# GRBLShieldv2.net
KiCad netlist of a schematic drawn in EAGLE
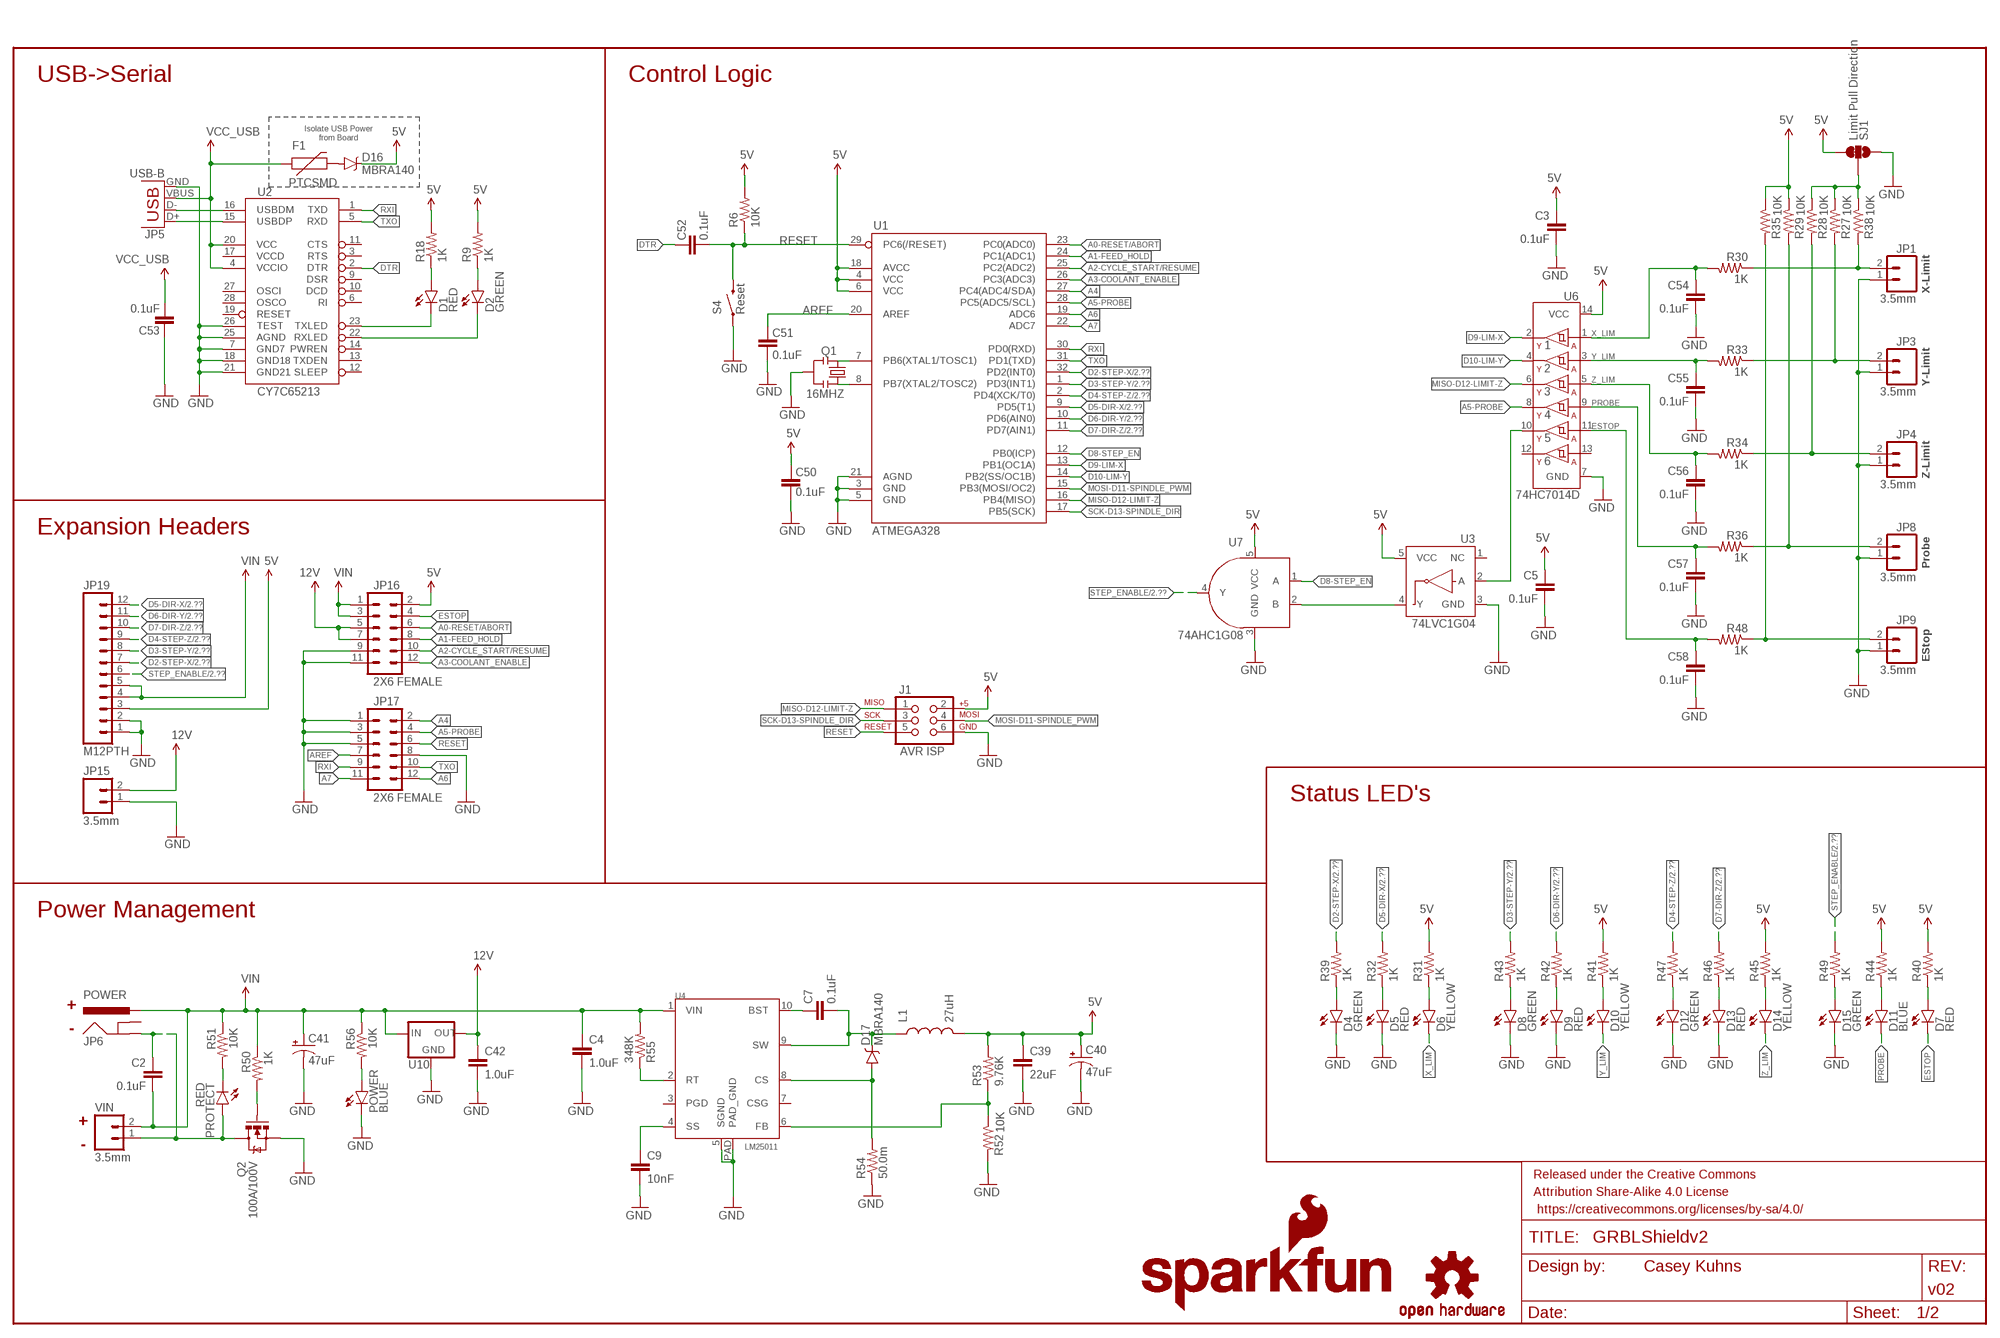
[diagram p0: schematic, sheet 1]
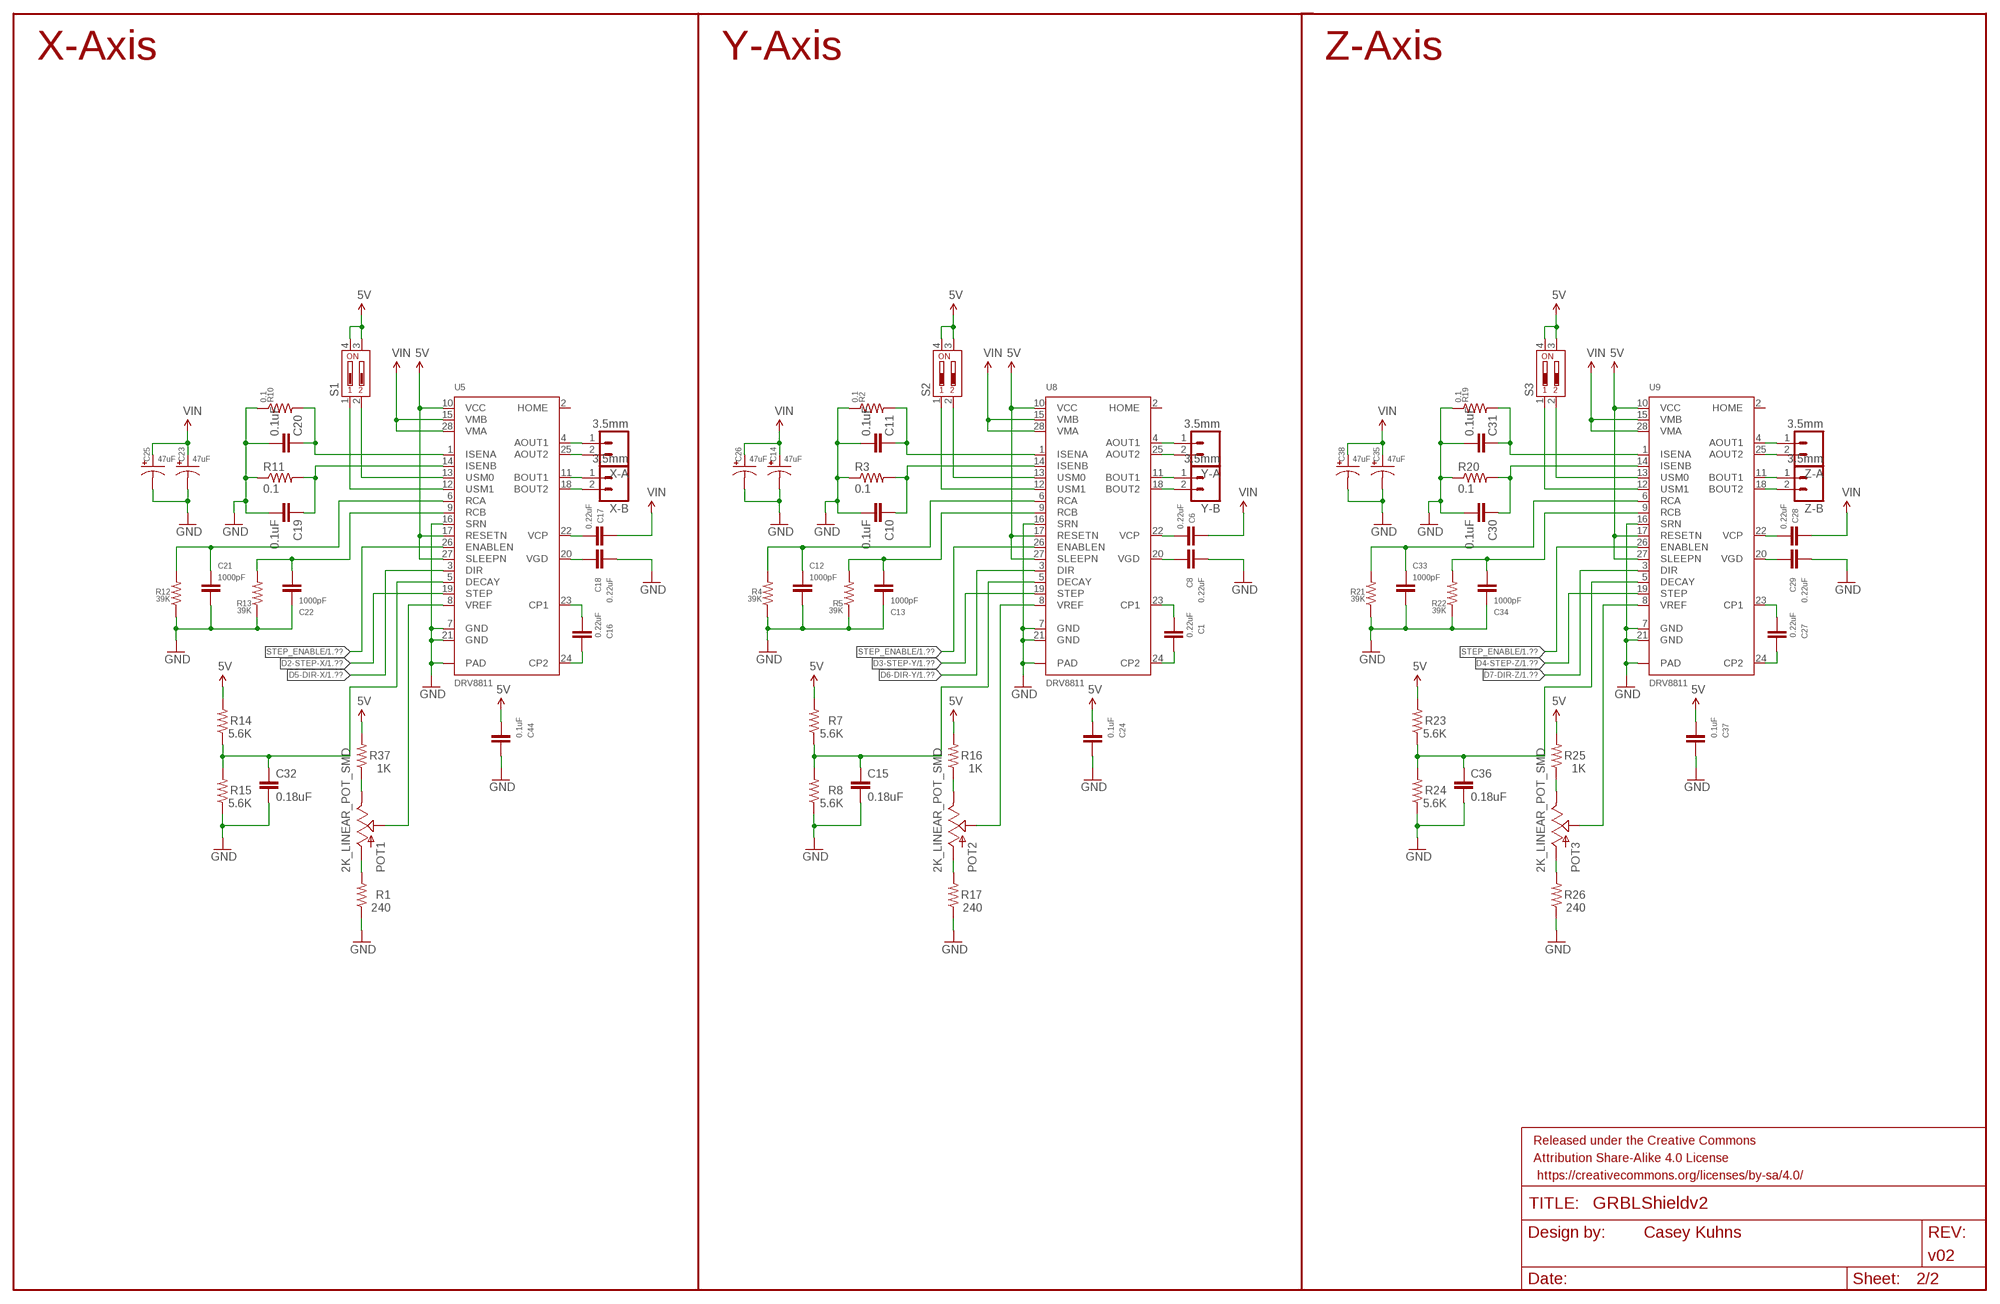
[diagram p1: schematic, sheet 2]

(export (version "E")
  (design (tool "Eeschema 10.0.6"))
  (components
    (comp (ref "C2")
      (value "0.1uF")
      (footprint "eagle-import:0603-CAP")
      (libsource (lib "eagle-import") (part "0.1UF-100V-10%(0603)"))
    )
    (comp (ref "C3")
      (value "0.1uF")
      (footprint "eagle-import:0603-CAP")
      (libsource (lib "eagle-import") (part "0.1UF-25V(+80/-20%)(0603)"))
    )
    (comp (ref "C4")
      (value "1.0uF")
      (footprint "eagle-import:1206")
      (libsource (lib "eagle-import") (part "1.0UF50V10%(1206)"))
    )
    (comp (ref "C5")
      (value "0.1uF")
      (footprint "eagle-import:0603-CAP")
      (libsource (lib "eagle-import") (part "0.1UF-25V(+80/-20%)(0603)"))
    )
    (comp (ref "C7")
      (value "0.1uF")
      (footprint "eagle-import:0603-CAP")
      (libsource (lib "eagle-import") (part "0.1UF-25V(+80/-20%)(0603)"))
    )
    (comp (ref "C9")
      (value "10nF")
      (footprint "eagle-import:0603-CAP")
      (libsource (lib "eagle-import") (part "10NF/10000PF-50V-10%(0603)"))
    )
    (comp (ref "C39")
      (value "22uF")
      (footprint "eagle-import:1210")
      (libsource (lib "eagle-import") (part "22UF-16V-20%-(1210)"))
    )
    (comp (ref "C40")
      (value "47uF")
      (footprint "eagle-import:PANASONIC_D")
      (libsource (lib "eagle-import") (part "47UF-50V-20%(ELECT)"))
    )
    (comp (ref "C41")
      (value "47uF")
      (footprint "eagle-import:PANASONIC_D")
      (libsource (lib "eagle-import") (part "47UF-50V-20%(ELECT)"))
    )
    (comp (ref "C42")
      (value "1.0uF")
      (footprint "eagle-import:1206")
      (libsource (lib "eagle-import") (part "1.0UF50V10%(1206)"))
    )
    (comp (ref "C50")
      (value "0.1uF")
      (footprint "eagle-import:0603-CAP")
      (libsource (lib "eagle-import") (part "0.1UF-25V(+80/-20%)(0603)"))
    )
    (comp (ref "C51")
      (value "0.1uF")
      (footprint "eagle-import:0603-CAP")
      (libsource (lib "eagle-import") (part "0.1UF-25V(+80/-20%)(0603)"))
    )
    (comp (ref "C52")
      (value "0.1uF")
      (footprint "eagle-import:0603-CAP")
      (libsource (lib "eagle-import") (part "0.1UF-25V(+80/-20%)(0603)"))
    )
    (comp (ref "C53")
      (value "0.1uF")
      (footprint "eagle-import:0603-CAP")
      (libsource (lib "eagle-import") (part "0.1UF-25V(+80/-20%)(0603)"))
    )
    (comp (ref "C54")
      (value "0.1uF")
      (footprint "eagle-import:0603-CAP")
      (libsource (lib "eagle-import") (part "0.1UF-25V(+80/-20%)(0603)"))
    )
    (comp (ref "C55")
      (value "0.1uF")
      (footprint "eagle-import:0603-CAP")
      (libsource (lib "eagle-import") (part "0.1UF-25V(+80/-20%)(0603)"))
    )
    (comp (ref "C56")
      (value "0.1uF")
      (footprint "eagle-import:0603-CAP")
      (libsource (lib "eagle-import") (part "0.1UF-25V(+80/-20%)(0603)"))
    )
    (comp (ref "C57")
      (value "0.1uF")
      (footprint "eagle-import:0603-CAP")
      (libsource (lib "eagle-import") (part "0.1UF-25V(+80/-20%)(0603)"))
    )
    (comp (ref "C58")
      (value "0.1uF")
      (footprint "eagle-import:0603-CAP")
      (libsource (lib "eagle-import") (part "0.1UF-25V(+80/-20%)(0603)"))
    )
    (comp (ref "D1")
      (value "RED")
      (footprint "eagle-import:LED-1206")
      (libsource (lib "eagle-import") (part "LED-REDLILYPAD"))
    )
    (comp (ref "D2")
      (value "GREEN")
      (footprint "eagle-import:LED-1206")
      (libsource (lib "eagle-import") (part "LED-GREENLILYPAD"))
    )
    (comp (ref "D4")
      (value "GREEN")
      (footprint "eagle-import:LED-1206")
      (libsource (lib "eagle-import") (part "LED-GREENLILYPAD"))
    )
    (comp (ref "D5")
      (value "RED")
      (footprint "eagle-import:LED-1206")
      (libsource (lib "eagle-import") (part "LED-REDLILYPAD"))
    )
    (comp (ref "D6")
      (value "YELLOW")
      (footprint "eagle-import:LED-1206")
      (libsource (lib "eagle-import") (part "LED-YELLOWLILYPAD"))
    )
    (comp (ref "D7")
      (value "RED")
      (footprint "eagle-import:LED-1206")
      (libsource (lib "eagle-import") (part "LED-REDLILYPAD"))
    )
    (comp (ref "D8")
      (value "GREEN")
      (footprint "eagle-import:LED-1206")
      (libsource (lib "eagle-import") (part "LED-GREENLILYPAD"))
    )
    (comp (ref "D9")
      (value "RED")
      (footprint "eagle-import:LED-1206")
      (libsource (lib "eagle-import") (part "LED-REDLILYPAD"))
    )
    (comp (ref "D10")
      (value "YELLOW")
      (footprint "eagle-import:LED-1206")
      (libsource (lib "eagle-import") (part "LED-YELLOWLILYPAD"))
    )
    (comp (ref "D11")
      (value "BLUE")
      (footprint "eagle-import:LED-1206")
      (libsource (lib "eagle-import") (part "LED-BLUE1206"))
    )
    (comp (ref "D12")
      (value "GREEN")
      (footprint "eagle-import:LED-1206")
      (libsource (lib "eagle-import") (part "LED-GREENLILYPAD"))
    )
    (comp (ref "D13")
      (value "RED")
      (footprint "eagle-import:LED-1206")
      (libsource (lib "eagle-import") (part "LED-REDLILYPAD"))
    )
    (comp (ref "D14")
      (value "YELLOW")
      (footprint "eagle-import:LED-1206")
      (libsource (lib "eagle-import") (part "LED-YELLOWLILYPAD"))
    )
    (comp (ref "D15")
      (value "GREEN")
      (footprint "eagle-import:LED-1206")
      (libsource (lib "eagle-import") (part "LED-GREENLILYPAD"))
    )
    (comp (ref "D16")
      (value "MBRA140")
      (footprint "eagle-import:SMA-DIODE")
      (libsource (lib "eagle-import") (part "DIODE-SCHOTTKY-MBRA140"))
    )
    (comp (ref "D17")
      (value "MBRA140")
      (footprint "eagle-import:SMA-DIODE")
      (libsource (lib "eagle-import") (part "DIODE-SCHOTTKY-MBRA140"))
    )
    (comp (ref "F1")
      (value "PTCSMD")
      (footprint "eagle-import:PTC-1206")
      (libsource (lib "eagle-import") (part "PTCSMD"))
    )
    (comp (ref "FRAME1")
      (value "FRAME-LEDGER")
      (footprint "eagle-import:CREATIVE_COMMONS")
      (fields (field (name "DESIGNER") "Casey Kuhns") (field (name "VERSION") "v02"))
      (libsource (lib "eagle-import") (part "FRAME-LEDGER"))
    )
    (comp (ref "J1")
      (value "AVR ISP")
      (footprint "eagle-import:2X3")
      (libsource (lib "eagle-import") (part "AVR_SPI_PRG_6PTH"))
    )
    (comp (ref "JP1")
      (value "3.5mm")
      (footprint "eagle-import:SCREWTERMINAL-3.5MM-2_LOCK")
      (libsource (lib "eagle-import") (part "M023.5MM_LOCK"))
    )
    (comp (ref "JP3")
      (value "3.5mm")
      (footprint "eagle-import:SCREWTERMINAL-3.5MM-2_LOCK")
      (libsource (lib "eagle-import") (part "M023.5MM_LOCK"))
    )
    (comp (ref "JP4")
      (value "3.5mm")
      (footprint "eagle-import:SCREWTERMINAL-3.5MM-2_LOCK")
      (libsource (lib "eagle-import") (part "M023.5MM_LOCK"))
    )
    (comp (ref "JP5")
      (value "USB-B")
      (footprint "eagle-import:USB-B-PTH")
      (libsource (lib "eagle-import") (part "USBPTH"))
    )
    (comp (ref "JP6")
      (value "POWER")
      (footprint "eagle-import:POWER_JACK_PTH_LOCK")
      (libsource (lib "eagle-import") (part "POWER_JACKPTH_LOCK"))
    )
    (comp (ref "JP8")
      (value "3.5mm")
      (footprint "eagle-import:SCREWTERMINAL-3.5MM-2_LOCK")
      (libsource (lib "eagle-import") (part "M023.5MM_LOCK"))
    )
    (comp (ref "JP9")
      (value "3.5mm")
      (footprint "eagle-import:SCREWTERMINAL-3.5MM-2_LOCK")
      (libsource (lib "eagle-import") (part "M023.5MM_LOCK"))
    )
    (comp (ref "JP15")
      (value "3.5mm")
      (footprint "eagle-import:SCREWTERMINAL-3.5MM-2_LOCK")
      (libsource (lib "eagle-import") (part "M023.5MM_LOCK"))
    )
    (comp (ref "JP16")
      (value "2X6 FEMALE")
      (footprint "eagle-import:2X6")
      (libsource (lib "eagle-import") (part "M06X2PTH_FEMALE"))
    )
    (comp (ref "JP17")
      (value "2X6 FEMALE")
      (footprint "eagle-import:2X6")
      (libsource (lib "eagle-import") (part "M06X2PTH_FEMALE"))
    )
    (comp (ref "JP19")
      (value "M12PTH")
      (footprint "eagle-import:1X12")
      (libsource (lib "eagle-import") (part "M12PTH"))
    )
    (comp (ref "L1")
      (value "27uH")
      (footprint "eagle-import:INDUCTOR_SDR1307")
      (libsource (lib "eagle-import") (part "INDUCTORSDR13-7-270ML"))
    )
    (comp (ref "LOGO1")
      (value "OSHW-LOGOM")
      (footprint "eagle-import:OSHW-LOGO-M")
      (libsource (lib "eagle-import") (part "OSHW-LOGOM"))
    )
    (comp (ref "LOGO2")
      (value "SFE_LOGO_NAME_FLAME.2_INCH")
      (footprint "eagle-import:SFE_LOGO_NAME_FLAME_.2")
      (libsource (lib "eagle-import") (part "SFE_LOGO_NAME_FLAME.2_INCH"))
    )
    (comp (ref "POWER")
      (value "BLUE")
      (footprint "eagle-import:LED-1206")
      (libsource (lib "eagle-import") (part "LED-BLUE1206"))
    )
    (comp (ref "PROTECT")
      (value "RED")
      (footprint "eagle-import:LED-1206")
      (libsource (lib "eagle-import") (part "LED-REDLILYPAD"))
    )
    (comp (ref "Q1")
      (value "16MHZ")
      (footprint "eagle-import:RESONATOR-SMD")
      (libsource (lib "eagle-import") (part "RESONATOR16MHZ"))
    )
    (comp (ref "Q2")
      (value "100A/100V")
      (footprint "eagle-import:TO-263_D2PAK")
      (libsource (lib "eagle-import") (part "MOSFET-NCHANNELPSMN7R0"))
    )
    (comp (ref "R6")
      (value "10K")
      (footprint "eagle-import:0603-RES")
      (libsource (lib "eagle-import") (part "10KOHM-1/10W-1%(0603)0603"))
    )
    (comp (ref "R9")
      (value "1K")
      (footprint "eagle-import:0603-RES")
      (libsource (lib "eagle-import") (part "1KOHM1/10W1%(0603)"))
    )
    (comp (ref "R18")
      (value "1K")
      (footprint "eagle-import:0603-RES")
      (libsource (lib "eagle-import") (part "1KOHM1/10W1%(0603)"))
    )
    (comp (ref "R27")
      (value "10K")
      (footprint "eagle-import:0603-RES")
      (libsource (lib "eagle-import") (part "10KOHM-1/10W-1%(0603)0603"))
    )
    (comp (ref "R28")
      (value "10K")
      (footprint "eagle-import:0603-RES")
      (libsource (lib "eagle-import") (part "10KOHM-1/10W-1%(0603)0603"))
    )
    (comp (ref "R29")
      (value "10K")
      (footprint "eagle-import:0603-RES")
      (libsource (lib "eagle-import") (part "10KOHM-1/10W-1%(0603)0603"))
    )
    (comp (ref "R30")
      (value "1K")
      (footprint "eagle-import:0603-RES")
      (libsource (lib "eagle-import") (part "1KOHM1/10W1%(0603)"))
    )
    (comp (ref "R31")
      (value "1K")
      (footprint "eagle-import:0603-RES")
      (libsource (lib "eagle-import") (part "1KOHM-1/10W-1%(0603)"))
    )
    (comp (ref "R32")
      (value "1K")
      (footprint "eagle-import:0603-RES")
      (libsource (lib "eagle-import") (part "1KOHM-1/10W-1%(0603)"))
    )
    (comp (ref "R33")
      (value "1K")
      (footprint "eagle-import:0603-RES")
      (libsource (lib "eagle-import") (part "1KOHM1/10W1%(0603)"))
    )
    (comp (ref "R34")
      (value "1K")
      (footprint "eagle-import:0603-RES")
      (libsource (lib "eagle-import") (part "1KOHM1/10W1%(0603)"))
    )
    (comp (ref "R35")
      (value "10K")
      (footprint "eagle-import:0603-RES")
      (libsource (lib "eagle-import") (part "10KOHM-1/10W-1%(0603)0603"))
    )
    (comp (ref "R36")
      (value "1K")
      (footprint "eagle-import:0603-RES")
      (libsource (lib "eagle-import") (part "1KOHM1/10W1%(0603)"))
    )
    (comp (ref "R38")
      (value "10K")
      (footprint "eagle-import:0603-RES")
      (libsource (lib "eagle-import") (part "10KOHM-1/10W-1%(0603)0603"))
    )
    (comp (ref "R39")
      (value "1K")
      (footprint "eagle-import:0603-RES")
      (libsource (lib "eagle-import") (part "1KOHM-1/10W-1%(0603)"))
    )
    (comp (ref "R40")
      (value "1K")
      (footprint "eagle-import:0603-RES")
      (libsource (lib "eagle-import") (part "1KOHM-1/10W-1%(0603)"))
    )
    (comp (ref "R41")
      (value "1K")
      (footprint "eagle-import:0603-RES")
      (libsource (lib "eagle-import") (part "1KOHM-1/10W-1%(0603)"))
    )
    (comp (ref "R42")
      (value "1K")
      (footprint "eagle-import:0603-RES")
      (libsource (lib "eagle-import") (part "1KOHM-1/10W-1%(0603)"))
    )
    (comp (ref "R43")
      (value "1K")
      (footprint "eagle-import:0603-RES")
      (libsource (lib "eagle-import") (part "1KOHM-1/10W-1%(0603)"))
    )
    (comp (ref "R44")
      (value "1K")
      (footprint "eagle-import:0603-RES")
      (libsource (lib "eagle-import") (part "1KOHM-1/10W-1%(0603)"))
    )
    (comp (ref "R45")
      (value "1K")
      (footprint "eagle-import:0603-RES")
      (libsource (lib "eagle-import") (part "1KOHM-1/10W-1%(0603)"))
    )
    (comp (ref "R46")
      (value "1K")
      (footprint "eagle-import:0603-RES")
      (libsource (lib "eagle-import") (part "1KOHM-1/10W-1%(0603)"))
    )
    (comp (ref "R47")
      (value "1K")
      (footprint "eagle-import:0603-RES")
      (libsource (lib "eagle-import") (part "1KOHM-1/10W-1%(0603)"))
    )
    (comp (ref "R48")
      (value "1K")
      (footprint "eagle-import:0603-RES")
      (libsource (lib "eagle-import") (part "1KOHM1/10W1%(0603)"))
    )
    (comp (ref "R49")
      (value "1K")
      (footprint "eagle-import:0603-RES")
      (libsource (lib "eagle-import") (part "1KOHM-1/10W-1%(0603)"))
    )
    (comp (ref "R50")
      (value "1K")
      (footprint "eagle-import:0603-RES")
      (libsource (lib "eagle-import") (part "1KOHM1/10W1%(0603)"))
    )
    (comp (ref "R51")
      (value "10K")
      (footprint "eagle-import:0603-RES")
      (libsource (lib "eagle-import") (part "10KOHM-1/10W-1%(0603)0603"))
    )
    (comp (ref "R52")
      (value "10K")
      (footprint "eagle-import:0603-RES")
      (libsource (lib "eagle-import") (part "10KOHM-1/10W-1%(0603)0603"))
    )
    (comp (ref "R53")
      (value "9.76K")
      (footprint "eagle-import:0603-RES")
      (libsource (lib "eagle-import") (part "RESISTOR0603-RES"))
    )
    (comp (ref "R54")
      (value "50.0m")
      (footprint "eagle-import:0603-RES")
      (libsource (lib "eagle-import") (part "RESISTOR0603-RES"))
    )
    (comp (ref "R55")
      (value "348K")
      (footprint "eagle-import:0603-RES")
      (libsource (lib "eagle-import") (part "RESISTOR0603-RES"))
    )
    (comp (ref "R56")
      (value "10K")
      (footprint "eagle-import:0603-RES")
      (libsource (lib "eagle-import") (part "10KOHM-1/10W-1%(0603)0603"))
    )
    (comp (ref "S4")
      (value "Reset")
      (footprint "eagle-import:TACTILE-SWITCH-SMD")
      (libsource (lib "eagle-import") (part "SWITCH-MOMENTARY-2SMD"))
    )
    (comp (ref "SJ1")
      (value "Limit Pull Direction")
      (footprint "eagle-import:PAD-JUMPER-3-2OF3_NC_BY_TRACE_YES_SILK_LARGE")
      (libsource (lib "eagle-import") (part "JUMPER-PAD-3-2OF3_NC_BY_TRACE_LARGE"))
    )
    (comp (ref "U1")
      (value "ATMEGA328")
      (footprint "eagle-import:TQFP32-08")
      (libsource (lib "eagle-import") (part "ATMEGA328_SMT"))
    )
    (comp (ref "U2")
      (value "CY7C65213")
      (footprint "eagle-import:SSOP28DB")
      (libsource (lib "eagle-import") (part "CY7C65213"))
    )
    (comp (ref "U3")
      (value "74LVC1G04")
      (footprint "eagle-import:SOT353")
      (libsource (lib "eagle-import") (part "INVERTER_SOT353-5"))
    )
    (comp (ref "U4")
      (value "LM25011")
      (footprint "eagle-import:HVSS0P-10")
      (libsource (lib "eagle-import") (part "LM25011"))
    )
    (comp (ref "U6")
      (value "74HC7014D")
      (footprint "eagle-import:SOIC-14")
      (libsource (lib "eagle-import") (part "74HC7014D"))
    )
    (comp (ref "U7")
      (value "74AHC1G08")
      (footprint "eagle-import:SOT23-5")
      (libsource (lib "eagle-import") (part "74AHC1G08"))
    )
    (comp (ref "U10")
      (value "V_REG_78XX7812")
      (footprint "eagle-import:TO-252")
      (libsource (lib "eagle-import") (part "V_REG_78XX7812"))
    )
    (comp (ref "VIN")
      (value "3.5mm")
      (footprint "eagle-import:SCREWTERMINAL-3.5MM-2_LOCK")
      (libsource (lib "eagle-import") (part "M023.5MM_LOCK"))
    )
    (comp (ref "C1")
      (value "0.22uF")
      (footprint "eagle-import:0603-CAP")
      (libsource (lib "eagle-import") (part "0.22UF50V-20%,+80%(0603)"))
    )
    (comp (ref "C6")
      (value "0.22uF")
      (footprint "eagle-import:0603-CAP")
      (libsource (lib "eagle-import") (part "0.22UF50V-20%,+80%(0603)"))
    )
    (comp (ref "C8")
      (value "0.22uF")
      (footprint "eagle-import:0603-CAP")
      (libsource (lib "eagle-import") (part "0.22UF50V-20%,+80%(0603)"))
    )
    (comp (ref "C10")
      (value "0.1uF")
      (footprint "eagle-import:0603-CAP")
      (libsource (lib "eagle-import") (part "0.1UF-25V(+80/-20%)(0603)"))
    )
    (comp (ref "C11")
      (value "0.1uF")
      (footprint "eagle-import:0603-CAP")
      (libsource (lib "eagle-import") (part "0.1UF-25V(+80/-20%)(0603)"))
    )
    (comp (ref "C12")
      (value "1000pF")
      (footprint "eagle-import:0603-CAP")
      (libsource (lib "eagle-import") (part "1NF/1000PF-50V-10%(0603)"))
    )
    (comp (ref "C13")
      (value "1000pF")
      (footprint "eagle-import:0603-CAP")
      (libsource (lib "eagle-import") (part "1NF/1000PF-50V-10%(0603)"))
    )
    (comp (ref "C14")
      (value "47uF")
      (footprint "eagle-import:PANASONIC_D")
      (libsource (lib "eagle-import") (part "47UF-50V-20%(ELECT)"))
    )
    (comp (ref "C15")
      (value "0.18uF")
      (footprint "eagle-import:0603-CAP")
      (libsource (lib "eagle-import") (part "CAP0603-CAP"))
    )
    (comp (ref "C16")
      (value "0.22uF")
      (footprint "eagle-import:0603-CAP")
      (libsource (lib "eagle-import") (part "0.22UF50V-20%,+80%(0603)"))
    )
    (comp (ref "C17")
      (value "0.22uF")
      (footprint "eagle-import:0603-CAP")
      (libsource (lib "eagle-import") (part "0.22UF50V-20%,+80%(0603)"))
    )
    (comp (ref "C18")
      (value "0.22uF")
      (footprint "eagle-import:0603-CAP")
      (libsource (lib "eagle-import") (part "0.22UF50V-20%,+80%(0603)"))
    )
    (comp (ref "C19")
      (value "0.1uF")
      (footprint "eagle-import:0603-CAP")
      (libsource (lib "eagle-import") (part "0.1UF-25V(+80/-20%)(0603)"))
    )
    (comp (ref "C20")
      (value "0.1uF")
      (footprint "eagle-import:0603-CAP")
      (libsource (lib "eagle-import") (part "0.1UF-25V(+80/-20%)(0603)"))
    )
    (comp (ref "C21")
      (value "1000pF")
      (footprint "eagle-import:0603-CAP")
      (libsource (lib "eagle-import") (part "1NF/1000PF-50V-10%(0603)"))
    )
    (comp (ref "C22")
      (value "1000pF")
      (footprint "eagle-import:0603-CAP")
      (libsource (lib "eagle-import") (part "1NF/1000PF-50V-10%(0603)"))
    )
    (comp (ref "C23")
      (value "47uF")
      (footprint "eagle-import:PANASONIC_D")
      (libsource (lib "eagle-import") (part "47UF-50V-20%(ELECT)"))
    )
    (comp (ref "C24")
      (value "0.1uF")
      (footprint "eagle-import:0603-CAP")
      (libsource (lib "eagle-import") (part "0.1UF-25V(+80/-20%)(0603)"))
    )
    (comp (ref "C25")
      (value "47uF")
      (footprint "eagle-import:PANASONIC_D")
      (libsource (lib "eagle-import") (part "47UF-50V-20%(ELECT)"))
    )
    (comp (ref "C26")
      (value "47uF")
      (footprint "eagle-import:PANASONIC_D")
      (libsource (lib "eagle-import") (part "47UF-50V-20%(ELECT)"))
    )
    (comp (ref "C27")
      (value "0.22uF")
      (footprint "eagle-import:0603-CAP")
      (libsource (lib "eagle-import") (part "0.22UF50V-20%,+80%(0603)"))
    )
    (comp (ref "C28")
      (value "0.22uF")
      (footprint "eagle-import:0603-CAP")
      (libsource (lib "eagle-import") (part "0.22UF50V-20%,+80%(0603)"))
    )
    (comp (ref "C29")
      (value "0.22uF")
      (footprint "eagle-import:0603-CAP")
      (libsource (lib "eagle-import") (part "0.22UF50V-20%,+80%(0603)"))
    )
    (comp (ref "C30")
      (value "0.1uF")
      (footprint "eagle-import:0603-CAP")
      (libsource (lib "eagle-import") (part "0.1UF-25V(+80/-20%)(0603)"))
    )
    (comp (ref "C31")
      (value "0.1uF")
      (footprint "eagle-import:0603-CAP")
      (libsource (lib "eagle-import") (part "0.1UF-25V(+80/-20%)(0603)"))
    )
    (comp (ref "C32")
      (value "0.18uF")
      (footprint "eagle-import:0603-CAP")
      (libsource (lib "eagle-import") (part "CAP0603-CAP"))
    )
    (comp (ref "C33")
      (value "1000pF")
      (footprint "eagle-import:0603-CAP")
      (libsource (lib "eagle-import") (part "1NF/1000PF-50V-10%(0603)"))
    )
    (comp (ref "C34")
      (value "1000pF")
      (footprint "eagle-import:0603-CAP")
      (libsource (lib "eagle-import") (part "1NF/1000PF-50V-10%(0603)"))
    )
    (comp (ref "C35")
      (value "47uF")
      (footprint "eagle-import:PANASONIC_D")
      (libsource (lib "eagle-import") (part "47UF-50V-20%(ELECT)"))
    )
    (comp (ref "C36")
      (value "0.18uF")
      (footprint "eagle-import:0603-CAP")
      (libsource (lib "eagle-import") (part "CAP0603-CAP"))
    )
    (comp (ref "C37")
      (value "0.1uF")
      (footprint "eagle-import:0603-CAP")
      (libsource (lib "eagle-import") (part "0.1UF-25V(+80/-20%)(0603)"))
    )
    (comp (ref "C38")
      (value "47uF")
      (footprint "eagle-import:PANASONIC_D")
      (libsource (lib "eagle-import") (part "47UF-50V-20%(ELECT)"))
    )
    (comp (ref "C44")
      (value "0.1uF")
      (footprint "eagle-import:0603-CAP")
      (libsource (lib "eagle-import") (part "0.1UF-25V(+80/-20%)(0603)"))
    )
    (comp (ref "FRAME2")
      (value "FRAME-LEDGER")
      (footprint "eagle-import:CREATIVE_COMMONS")
      (fields (field (name "DESIGNER") "Casey Kuhns") (field (name "VERSION") "v02"))
      (libsource (lib "eagle-import") (part "FRAME-LEDGER"))
    )
    (comp (ref "POT1")
      (value "2K_LINEAR_POT_SMD")
      (footprint "eagle-import:TC33X")
      (libsource (lib "eagle-import") (part "2K_LINEAR_POT_SMD"))
    )
    (comp (ref "POT2")
      (value "2K_LINEAR_POT_SMD")
      (footprint "eagle-import:TC33X")
      (libsource (lib "eagle-import") (part "2K_LINEAR_POT_SMD"))
    )
    (comp (ref "POT3")
      (value "2K_LINEAR_POT_SMD")
      (footprint "eagle-import:TC33X")
      (libsource (lib "eagle-import") (part "2K_LINEAR_POT_SMD"))
    )
    (comp (ref "R1")
      (value "240")
      (footprint "eagle-import:0603-RES")
      (libsource (lib "eagle-import") (part "240OHM1/10W1%(0603)"))
    )
    (comp (ref "R2")
      (value "0.1")
      (footprint "eagle-import:1210")
      (libsource (lib "eagle-import") (part "0.1OHM-1/2W-1%(1210)"))
    )
    (comp (ref "R3")
      (value "0.1")
      (footprint "eagle-import:1210")
      (libsource (lib "eagle-import") (part "0.1OHM-1/2W-1%(1210)"))
    )
    (comp (ref "R4")
      (value "39K")
      (footprint "eagle-import:0603")
      (libsource (lib "eagle-import") (part "39KOHM-1/10W-1%(0603)"))
    )
    (comp (ref "R5")
      (value "39K")
      (footprint "eagle-import:0603")
      (libsource (lib "eagle-import") (part "39KOHM-1/10W-1%(0603)"))
    )
    (comp (ref "R7")
      (value "5.6K")
      (footprint "eagle-import:0603")
      (libsource (lib "eagle-import") (part "5.6KOHM-1/10W-1%(0603)"))
    )
    (comp (ref "R8")
      (value "5.6K")
      (footprint "eagle-import:0603")
      (libsource (lib "eagle-import") (part "5.6KOHM-1/10W-1%(0603)"))
    )
    (comp (ref "R10")
      (value "0.1")
      (footprint "eagle-import:1210")
      (libsource (lib "eagle-import") (part "0.1OHM-1/2W-1%(1210)"))
    )
    (comp (ref "R11")
      (value "0.1")
      (footprint "eagle-import:1210")
      (libsource (lib "eagle-import") (part "0.1OHM-1/2W-1%(1210)"))
    )
    (comp (ref "R12")
      (value "39K")
      (footprint "eagle-import:0603")
      (libsource (lib "eagle-import") (part "39KOHM-1/10W-1%(0603)"))
    )
    (comp (ref "R13")
      (value "39K")
      (footprint "eagle-import:0603")
      (libsource (lib "eagle-import") (part "39KOHM-1/10W-1%(0603)"))
    )
    (comp (ref "R14")
      (value "5.6K")
      (footprint "eagle-import:0603")
      (libsource (lib "eagle-import") (part "5.6KOHM-1/10W-1%(0603)"))
    )
    (comp (ref "R15")
      (value "5.6K")
      (footprint "eagle-import:0603")
      (libsource (lib "eagle-import") (part "5.6KOHM-1/10W-1%(0603)"))
    )
    (comp (ref "R16")
      (value "1K")
      (footprint "eagle-import:0603-RES")
      (libsource (lib "eagle-import") (part "1KOHM-1/10W-1%(0603)"))
    )
    (comp (ref "R17")
      (value "240")
      (footprint "eagle-import:0603-RES")
      (libsource (lib "eagle-import") (part "240OHM1/10W1%(0603)"))
    )
    (comp (ref "R19")
      (value "0.1")
      (footprint "eagle-import:1210")
      (libsource (lib "eagle-import") (part "0.1OHM-1/2W-1%(1210)"))
    )
    (comp (ref "R20")
      (value "0.1")
      (footprint "eagle-import:1210")
      (libsource (lib "eagle-import") (part "0.1OHM-1/2W-1%(1210)"))
    )
    (comp (ref "R21")
      (value "39K")
      (footprint "eagle-import:0603")
      (libsource (lib "eagle-import") (part "39KOHM-1/10W-1%(0603)"))
    )
    (comp (ref "R22")
      (value "39K")
      (footprint "eagle-import:0603")
      (libsource (lib "eagle-import") (part "39KOHM-1/10W-1%(0603)"))
    )
    (comp (ref "R23")
      (value "5.6K")
      (footprint "eagle-import:0603")
      (libsource (lib "eagle-import") (part "5.6KOHM-1/10W-1%(0603)"))
    )
    (comp (ref "R24")
      (value "5.6K")
      (footprint "eagle-import:0603")
      (libsource (lib "eagle-import") (part "5.6KOHM-1/10W-1%(0603)"))
    )
    (comp (ref "R25")
      (value "1K")
      (footprint "eagle-import:0603-RES")
      (libsource (lib "eagle-import") (part "1KOHM-1/10W-1%(0603)"))
    )
    (comp (ref "R26")
      (value "240")
      (footprint "eagle-import:0603-RES")
      (libsource (lib "eagle-import") (part "240OHM1/10W1%(0603)"))
    )
    (comp (ref "R37")
      (value "1K")
      (footprint "eagle-import:0603-RES")
      (libsource (lib "eagle-import") (part "1KOHM-1/10W-1%(0603)"))
    )
    (comp (ref "S1")
      (value "2-POS-DIP")
      (footprint "eagle-import:CHS-02A")
      (libsource (lib "eagle-import") (part "2-POS-DIP"))
    )
    (comp (ref "S2")
      (value "2-POS-DIP")
      (footprint "eagle-import:CHS-02A")
      (libsource (lib "eagle-import") (part "2-POS-DIP"))
    )
    (comp (ref "S3")
      (value "2-POS-DIP")
      (footprint "eagle-import:CHS-02A")
      (libsource (lib "eagle-import") (part "2-POS-DIP"))
    )
    (comp (ref "U5")
      (value "DRV8811")
      (footprint "eagle-import:HTSSOP28")
      (libsource (lib "eagle-import") (part "DRV8811"))
    )
    (comp (ref "U8")
      (value "DRV8811")
      (footprint "eagle-import:HTSSOP28")
      (libsource (lib "eagle-import") (part "DRV8811"))
    )
    (comp (ref "U9")
      (value "DRV8811")
      (footprint "eagle-import:HTSSOP28")
      (libsource (lib "eagle-import") (part "DRV8811"))
    )
    (comp (ref "X-A")
      (value "3.5mm")
      (footprint "eagle-import:SCREWTERMINAL-3.5MM-2_LOCK")
      (libsource (lib "eagle-import") (part "M023.5MM_LOCK"))
    )
    (comp (ref "X-B")
      (value "3.5mm")
      (footprint "eagle-import:SCREWTERMINAL-3.5MM-2_LOCK")
      (libsource (lib "eagle-import") (part "M023.5MM_LOCK"))
    )
    (comp (ref "Y-A")
      (value "3.5mm")
      (footprint "eagle-import:SCREWTERMINAL-3.5MM-2_LOCK")
      (libsource (lib "eagle-import") (part "M023.5MM_LOCK"))
    )
    (comp (ref "Y-B")
      (value "3.5mm")
      (footprint "eagle-import:SCREWTERMINAL-3.5MM-2_LOCK")
      (libsource (lib "eagle-import") (part "M023.5MM_LOCK"))
    )
    (comp (ref "Z-A")
      (value "3.5mm")
      (footprint "eagle-import:SCREWTERMINAL-3.5MM-2_LOCK")
      (libsource (lib "eagle-import") (part "M023.5MM_LOCK"))
    )
    (comp (ref "Z-B")
      (value "3.5mm")
      (footprint "eagle-import:SCREWTERMINAL-3.5MM-2_LOCK")
      (libsource (lib "eagle-import") (part "M023.5MM_LOCK"))
    )
  )
  (nets
    (net (code "1") (name "5V") (class "Default")
      (node (ref "C24") (pin "1") (pinfunction "1_1") (pintype "passive"))
      (node (ref "C3") (pin "1") (pinfunction "1_1") (pintype "passive"))
      (node (ref "C37") (pin "1") (pinfunction "1_1") (pintype "passive"))
      (node (ref "C39") (pin "1") (pinfunction "1_1") (pintype "passive"))
      (node (ref "C40") (pin "+") (pinfunction "+_+") (pintype "passive"))
      (node (ref "C44") (pin "1") (pinfunction "1_1") (pintype "passive"))
      (node (ref "C5") (pin "1") (pinfunction "1_1") (pintype "passive"))
      (node (ref "C50") (pin "2") (pinfunction "2_2") (pintype "passive"))
      (node (ref "D16") (pin "C") (pinfunction "C_C") (pintype "passive"))
      (node (ref "J1") (pin "2") (pinfunction "2_2") (pintype "passive"))
      (node (ref "JP16") (pin "2") (pinfunction "2_2") (pintype "passive"))
      (node (ref "JP19") (pin "3") (pinfunction "3_3") (pintype "passive"))
      (node (ref "L1") (pin "P$2") (pinfunction "2_P$2") (pintype "passive"))
      (node (ref "R14") (pin "2") (pinfunction "2_2") (pintype "passive"))
      (node (ref "R16") (pin "2") (pinfunction "2_2") (pintype "passive"))
      (node (ref "R18") (pin "2") (pinfunction "2_2") (pintype "passive"))
      (node (ref "R23") (pin "2") (pinfunction "2_2") (pintype "passive"))
      (node (ref "R25") (pin "2") (pinfunction "2_2") (pintype "passive"))
      (node (ref "R29") (pin "1") (pinfunction "1_1") (pintype "passive"))
      (node (ref "R31") (pin "2") (pinfunction "2_2") (pintype "passive"))
      (node (ref "R35") (pin "1") (pinfunction "1_1") (pintype "passive"))
      (node (ref "R37") (pin "2") (pinfunction "2_2") (pintype "passive"))
      (node (ref "R40") (pin "2") (pinfunction "2_2") (pintype "passive"))
      (node (ref "R41") (pin "2") (pinfunction "2_2") (pintype "passive"))
      (node (ref "R44") (pin "2") (pinfunction "2_2") (pintype "passive"))
      (node (ref "R45") (pin "2") (pinfunction "2_2") (pintype "passive"))
      (node (ref "R53") (pin "2") (pinfunction "2_2") (pintype "passive"))
      (node (ref "R6") (pin "2") (pinfunction "2_2") (pintype "passive"))
      (node (ref "R7") (pin "2") (pinfunction "2_2") (pintype "passive"))
      (node (ref "R9") (pin "2") (pinfunction "2_2") (pintype "passive"))
      (node (ref "S1") (pin "3") (pinfunction "P$3_3") (pintype "bidirectional"))
      (node (ref "S1") (pin "4") (pinfunction "P$4_4") (pintype "bidirectional"))
      (node (ref "S2") (pin "3") (pinfunction "P$3_3") (pintype "bidirectional"))
      (node (ref "S2") (pin "4") (pinfunction "P$4_4") (pintype "bidirectional"))
      (node (ref "S3") (pin "3") (pinfunction "P$3_3") (pintype "bidirectional"))
      (node (ref "S3") (pin "4") (pinfunction "P$4_4") (pintype "bidirectional"))
      (node (ref "SJ1") (pin "3") (pinfunction "3_3") (pintype "passive"))
      (node (ref "U1") (pin "18") (pinfunction "AVCC_18") (pintype "bidirectional"))
      (node (ref "U1") (pin "4") (pinfunction "VCC_4") (pintype "bidirectional"))
      (node (ref "U1") (pin "6") (pinfunction "VCC_6") (pintype "bidirectional"))
      (node (ref "U3") (pin "5") (pinfunction "VCC_5") (pintype "bidirectional"))
      (node (ref "U5") (pin "10") (pinfunction "VCC_10") (pintype "bidirectional"))
      (node (ref "U5") (pin "17") (pinfunction "RESETN_17") (pintype "bidirectional"))
      (node (ref "U5") (pin "27") (pinfunction "SLEEPN_27") (pintype "bidirectional"))
      (node (ref "U6") (pin "14") (pinfunction "VCC_14") (pintype "power_in"))
      (node (ref "U7") (pin "5") (pinfunction "VCC_5") (pintype "bidirectional"))
      (node (ref "U8") (pin "10") (pinfunction "VCC_10") (pintype "bidirectional"))
      (node (ref "U8") (pin "17") (pinfunction "RESETN_17") (pintype "bidirectional"))
      (node (ref "U8") (pin "27") (pinfunction "SLEEPN_27") (pintype "bidirectional"))
      (node (ref "U9") (pin "10") (pinfunction "VCC_10") (pintype "bidirectional"))
      (node (ref "U9") (pin "17") (pinfunction "RESETN_17") (pintype "bidirectional"))
      (node (ref "U9") (pin "27") (pinfunction "SLEEPN_27") (pintype "bidirectional"))
    )
    (net (code "2") (name "A0-RESET{slash}ABORT") (class "Default")
      (node (ref "JP16") (pin "6") (pinfunction "6_6") (pintype "passive"))
      (node (ref "U1") (pin "23") (pinfunction "PC0(ADC0)_23") (pintype "bidirectional"))
    )
    (net (code "3") (name "A1-FEED_HOLD") (class "Default")
      (node (ref "JP16") (pin "8") (pinfunction "8_8") (pintype "passive"))
      (node (ref "U1") (pin "24") (pinfunction "PC1(ADC1)_24") (pintype "bidirectional"))
    )
    (net (code "4") (name "A2-CYCLE_START{slash}RESUME") (class "Default")
      (node (ref "JP16") (pin "10") (pinfunction "10_10") (pintype "passive"))
      (node (ref "U1") (pin "25") (pinfunction "PC2(ADC2)_25") (pintype "bidirectional"))
    )
    (net (code "5") (name "A3-COOLANT_ENABLE") (class "Default")
      (node (ref "JP16") (pin "12") (pinfunction "12_12") (pintype "passive"))
      (node (ref "U1") (pin "26") (pinfunction "PC3(ADC3)_26") (pintype "bidirectional"))
    )
    (net (code "6") (name "A4") (class "Default")
      (node (ref "JP17") (pin "2") (pinfunction "2_2") (pintype "passive"))
      (node (ref "U1") (pin "27") (pinfunction "PC4(ADC4/SDA)_27") (pintype "bidirectional"))
    )
    (net (code "7") (name "A5-PROBE") (class "Default")
      (node (ref "JP17") (pin "4") (pinfunction "4_4") (pintype "passive"))
      (node (ref "U1") (pin "28") (pinfunction "PC5(ADC5/SCL)_28") (pintype "bidirectional"))
      (node (ref "U6") (pin "8") (pinfunction "4Y_8") (pintype "output"))
    )
    (net (code "8") (name "A6") (class "Default")
      (node (ref "JP17") (pin "12") (pinfunction "12_12") (pintype "passive"))
      (node (ref "U1") (pin "19") (pinfunction "ADC6_19") (pintype "bidirectional"))
    )
    (net (code "9") (name "A7") (class "Default")
      (node (ref "JP17") (pin "11") (pinfunction "11_11") (pintype "passive"))
      (node (ref "U1") (pin "22") (pinfunction "ADC7_22") (pintype "bidirectional"))
    )
    (net (code "10") (name "AREF") (class "Default")
      (node (ref "C51") (pin "2") (pinfunction "2_2") (pintype "passive"))
      (node (ref "JP17") (pin "7") (pinfunction "7_7") (pintype "passive"))
      (node (ref "U1") (pin "20") (pinfunction "AREF_20") (pintype "bidirectional"))
    )
    (net (code "11") (name "D2-STEP-X") (class "Default")
      (node (ref "JP19") (pin "7") (pinfunction "7_7") (pintype "passive"))
      (node (ref "R39") (pin "2") (pinfunction "2_2") (pintype "passive"))
      (node (ref "U1") (pin "32") (pinfunction "PD2(INT0)_32") (pintype "bidirectional"))
      (node (ref "U5") (pin "19") (pinfunction "STEP_19") (pintype "bidirectional"))
    )
    (net (code "12") (name "D3-STEP-Y") (class "Default")
      (node (ref "JP19") (pin "8") (pinfunction "8_8") (pintype "passive"))
      (node (ref "R43") (pin "2") (pinfunction "2_2") (pintype "passive"))
      (node (ref "U1") (pin "1") (pinfunction "PD3(INT1)_1") (pintype "bidirectional"))
      (node (ref "U8") (pin "19") (pinfunction "STEP_19") (pintype "bidirectional"))
    )
    (net (code "13") (name "D4-STEP-Z") (class "Default")
      (node (ref "JP19") (pin "9") (pinfunction "9_9") (pintype "passive"))
      (node (ref "R47") (pin "2") (pinfunction "2_2") (pintype "passive"))
      (node (ref "U1") (pin "2") (pinfunction "PD4(XCK/T0)_2") (pintype "bidirectional"))
      (node (ref "U9") (pin "19") (pinfunction "STEP_19") (pintype "bidirectional"))
    )
    (net (code "14") (name "D5-DIR-X") (class "Default")
      (node (ref "JP19") (pin "12") (pinfunction "12_12") (pintype "passive"))
      (node (ref "R32") (pin "2") (pinfunction "2_2") (pintype "passive"))
      (node (ref "U1") (pin "9") (pinfunction "PD5(T1)_9") (pintype "bidirectional"))
      (node (ref "U5") (pin "3") (pinfunction "DIR_3") (pintype "bidirectional"))
    )
    (net (code "15") (name "D6-DIR-Y") (class "Default")
      (node (ref "JP19") (pin "11") (pinfunction "11_11") (pintype "passive"))
      (node (ref "R42") (pin "2") (pinfunction "2_2") (pintype "passive"))
      (node (ref "U1") (pin "10") (pinfunction "PD6(AIN0)_10") (pintype "bidirectional"))
      (node (ref "U8") (pin "3") (pinfunction "DIR_3") (pintype "bidirectional"))
    )
    (net (code "16") (name "D7-DIR-Z") (class "Default")
      (node (ref "JP19") (pin "10") (pinfunction "10_10") (pintype "passive"))
      (node (ref "R46") (pin "2") (pinfunction "2_2") (pintype "passive"))
      (node (ref "U1") (pin "11") (pinfunction "PD7(AIN1)_11") (pintype "bidirectional"))
      (node (ref "U9") (pin "3") (pinfunction "DIR_3") (pintype "bidirectional"))
    )
    (net (code "17") (name "D8-STEP_EN") (class "Default")
      (node (ref "U1") (pin "12") (pinfunction "PB0(ICP)_12") (pintype "bidirectional"))
      (node (ref "U7") (pin "1") (pinfunction "A_1") (pintype "bidirectional"))
    )
    (net (code "18") (name "D9-LIM-X") (class "Default")
      (node (ref "U1") (pin "13") (pinfunction "PB1(OC1A)_13") (pintype "bidirectional"))
      (node (ref "U6") (pin "2") (pinfunction "1Y_2") (pintype "output"))
    )
    (net (code "19") (name "D10-LIM-Y") (class "Default")
      (node (ref "U1") (pin "14") (pinfunction "PB2(SS/OC1B)_14") (pintype "bidirectional"))
      (node (ref "U6") (pin "4") (pinfunction "2Y_4") (pintype "output"))
    )
    (net (code "20") (name "DTR") (class "Default")
      (node (ref "C52") (pin "2") (pinfunction "2_2") (pintype "passive"))
      (node (ref "U2") (pin "2") (pinfunction "DTR_2") (pintype "output"))
    )
    (net (code "21") (name "ESTOP") (class "Default")
      (node (ref "C58") (pin "1") (pinfunction "1_1") (pintype "passive"))
      (node (ref "D7") (pin "C") (pinfunction "C_C") (pintype "passive"))
      (node (ref "JP16") (pin "4") (pinfunction "4_4") (pintype "passive"))
      (node (ref "R48") (pin "2") (pinfunction "2_2") (pintype "passive"))
      (node (ref "U6") (pin "11") (pinfunction "5A_11") (pintype "input"))
    )
    (net (code "22") (name "GND") (class "Default")
      (node (ref "C10") (pin "2") (pinfunction "2_2") (pintype "passive"))
      (node (ref "C11") (pin "2") (pinfunction "2_2") (pintype "passive"))
      (node (ref "C12") (pin "2") (pinfunction "2_2") (pintype "passive"))
      (node (ref "C13") (pin "2") (pinfunction "2_2") (pintype "passive"))
      (node (ref "C14") (pin "-") (pinfunction "-_-") (pintype "passive"))
      (node (ref "C15") (pin "2") (pinfunction "2_2") (pintype "passive"))
      (node (ref "C18") (pin "1") (pinfunction "1_1") (pintype "passive"))
      (node (ref "C19") (pin "2") (pinfunction "2_2") (pintype "passive"))
      (node (ref "C20") (pin "2") (pinfunction "2_2") (pintype "passive"))
      (node (ref "C21") (pin "2") (pinfunction "2_2") (pintype "passive"))
      (node (ref "C22") (pin "2") (pinfunction "2_2") (pintype "passive"))
      (node (ref "C23") (pin "-") (pinfunction "-_-") (pintype "passive"))
      (node (ref "C24") (pin "2") (pinfunction "2_2") (pintype "passive"))
      (node (ref "C25") (pin "-") (pinfunction "-_-") (pintype "passive"))
      (node (ref "C26") (pin "-") (pinfunction "-_-") (pintype "passive"))
      (node (ref "C29") (pin "1") (pinfunction "1_1") (pintype "passive"))
      (node (ref "C3") (pin "2") (pinfunction "2_2") (pintype "passive"))
      (node (ref "C30") (pin "2") (pinfunction "2_2") (pintype "passive"))
      (node (ref "C31") (pin "2") (pinfunction "2_2") (pintype "passive"))
      (node (ref "C32") (pin "2") (pinfunction "2_2") (pintype "passive"))
      (node (ref "C33") (pin "2") (pinfunction "2_2") (pintype "passive"))
      (node (ref "C34") (pin "2") (pinfunction "2_2") (pintype "passive"))
      (node (ref "C35") (pin "-") (pinfunction "-_-") (pintype "passive"))
      (node (ref "C36") (pin "2") (pinfunction "2_2") (pintype "passive"))
      (node (ref "C37") (pin "2") (pinfunction "2_2") (pintype "passive"))
      (node (ref "C38") (pin "-") (pinfunction "-_-") (pintype "passive"))
      (node (ref "C39") (pin "2") (pinfunction "2_2") (pintype "passive"))
      (node (ref "C4") (pin "2") (pinfunction "2_2") (pintype "passive"))
      (node (ref "C40") (pin "-") (pinfunction "-_-") (pintype "passive"))
      (node (ref "C41") (pin "-") (pinfunction "-_-") (pintype "passive"))
      (node (ref "C42") (pin "2") (pinfunction "2_2") (pintype "passive"))
      (node (ref "C44") (pin "2") (pinfunction "2_2") (pintype "passive"))
      (node (ref "C5") (pin "2") (pinfunction "2_2") (pintype "passive"))
      (node (ref "C50") (pin "1") (pinfunction "1_1") (pintype "passive"))
      (node (ref "C51") (pin "1") (pinfunction "1_1") (pintype "passive"))
      (node (ref "C53") (pin "2") (pinfunction "2_2") (pintype "passive"))
      (node (ref "C54") (pin "2") (pinfunction "2_2") (pintype "passive"))
      (node (ref "C55") (pin "2") (pinfunction "2_2") (pintype "passive"))
      (node (ref "C56") (pin "2") (pinfunction "2_2") (pintype "passive"))
      (node (ref "C57") (pin "2") (pinfunction "2_2") (pintype "passive"))
      (node (ref "C58") (pin "2") (pinfunction "2_2") (pintype "passive"))
      (node (ref "C8") (pin "1") (pinfunction "1_1") (pintype "passive"))
      (node (ref "C9") (pin "2") (pinfunction "2_2") (pintype "passive"))
      (node (ref "D12") (pin "C") (pinfunction "C_C") (pintype "passive"))
      (node (ref "D13") (pin "C") (pinfunction "C_C") (pintype "passive"))
      (node (ref "D15") (pin "C") (pinfunction "C_C") (pintype "passive"))
      (node (ref "D4") (pin "C") (pinfunction "C_C") (pintype "passive"))
      (node (ref "D5") (pin "C") (pinfunction "C_C") (pintype "passive"))
      (node (ref "D8") (pin "C") (pinfunction "C_C") (pintype "passive"))
      (node (ref "D9") (pin "C") (pinfunction "C_C") (pintype "passive"))
      (node (ref "J1") (pin "6") (pinfunction "6_6") (pintype "passive"))
      (node (ref "JP1") (pin "1") (pinfunction "1_1") (pintype "passive"))
      (node (ref "JP15") (pin "1") (pinfunction "1_1") (pintype "passive"))
      (node (ref "JP16") (pin "11") (pinfunction "11_11") (pintype "passive"))
      (node (ref "JP16") (pin "9") (pinfunction "9_9") (pintype "passive"))
      (node (ref "JP17") (pin "1") (pinfunction "1_1") (pintype "passive"))
      (node (ref "JP17") (pin "3") (pinfunction "3_3") (pintype "passive"))
      (node (ref "JP17") (pin "5") (pinfunction "5_5") (pintype "passive"))
      (node (ref "JP17") (pin "8") (pinfunction "8_8") (pintype "passive"))
      (node (ref "JP19") (pin "1") (pinfunction "1_1") (pintype "passive"))
      (node (ref "JP19") (pin "2") (pinfunction "2_2") (pintype "passive"))
      (node (ref "JP3") (pin "1") (pinfunction "1_1") (pintype "passive"))
      (node (ref "JP4") (pin "1") (pinfunction "1_1") (pintype "passive"))
      (node (ref "JP5") (pin "GND") (pinfunction "GND_GND") (pintype "bidirectional"))
      (node (ref "JP8") (pin "1") (pinfunction "1_1") (pintype "passive"))
      (node (ref "JP9") (pin "1") (pinfunction "1_1") (pintype "passive"))
      (node (ref "POWER") (pin "C") (pinfunction "C_C") (pintype "passive"))
      (node (ref "Q1") (pin "2") (pinfunction "2_2") (pintype "passive"))
      (node (ref "Q2") (pin "3") (pinfunction "S_3") (pintype "passive"))
      (node (ref "R1") (pin "1") (pinfunction "1_1") (pintype "passive"))
      (node (ref "R10") (pin "1") (pinfunction "1_1") (pintype "passive"))
      (node (ref "R11") (pin "1") (pinfunction "1_1") (pintype "passive"))
      (node (ref "R12") (pin "1") (pinfunction "1_1") (pintype "passive"))
      (node (ref "R13") (pin "1") (pinfunction "1_1") (pintype "passive"))
      (node (ref "R15") (pin "1") (pinfunction "1_1") (pintype "passive"))
      (node (ref "R17") (pin "1") (pinfunction "1_1") (pintype "passive"))
      (node (ref "R19") (pin "1") (pinfunction "1_1") (pintype "passive"))
      (node (ref "R2") (pin "1") (pinfunction "1_1") (pintype "passive"))
      (node (ref "R20") (pin "1") (pinfunction "1_1") (pintype "passive"))
      (node (ref "R21") (pin "1") (pinfunction "1_1") (pintype "passive"))
      (node (ref "R22") (pin "1") (pinfunction "1_1") (pintype "passive"))
      (node (ref "R24") (pin "1") (pinfunction "1_1") (pintype "passive"))
      (node (ref "R26") (pin "1") (pinfunction "1_1") (pintype "passive"))
      (node (ref "R3") (pin "1") (pinfunction "1_1") (pintype "passive"))
      (node (ref "R4") (pin "1") (pinfunction "1_1") (pintype "passive"))
      (node (ref "R5") (pin "1") (pinfunction "1_1") (pintype "passive"))
      (node (ref "R52") (pin "2") (pinfunction "2_2") (pintype "passive"))
      (node (ref "R54") (pin "1") (pinfunction "1_1") (pintype "passive"))
      (node (ref "R8") (pin "1") (pinfunction "1_1") (pintype "passive"))
      (node (ref "S4") (pin "1") (pinfunction "1_1") (pintype "passive"))
      (node (ref "SJ1") (pin "1") (pinfunction "1_1") (pintype "passive"))
      (node (ref "U1") (pin "21") (pinfunction "AGND_21") (pintype "bidirectional"))
      (node (ref "U1") (pin "3") (pinfunction "GND_3") (pintype "bidirectional"))
      (node (ref "U1") (pin "5") (pinfunction "GND_5") (pintype "bidirectional"))
      (node (ref "U10") (pin "3") (pinfunction "GND_3") (pintype "input"))
      (node (ref "U2") (pin "18") (pinfunction "GND18_18") (pintype "power_in"))
      (node (ref "U2") (pin "21") (pinfunction "GND21_21") (pintype "power_in"))
      (node (ref "U2") (pin "25") (pinfunction "AGND_25") (pintype "power_in"))
      (node (ref "U2") (pin "26") (pinfunction "TEST_26") (pintype "input"))
      (node (ref "U2") (pin "7") (pinfunction "GND7_7") (pintype "power_in"))
      (node (ref "U3") (pin "3") (pinfunction "GND_3") (pintype "bidirectional"))
      (node (ref "U4") (pin "5") (pinfunction "SGND_5") (pintype "bidirectional"))
      (node (ref "U4") (pin "PAD") (pinfunction "PAD_GND_PAD") (pintype "bidirectional"))
      (node (ref "U5") (pin "16") (pinfunction "SRN_16") (pintype "bidirectional"))
      (node (ref "U5") (pin "21") (pinfunction "GND_21") (pintype "bidirectional"))
      (node (ref "U5") (pin "7") (pinfunction "GND_7") (pintype "bidirectional"))
      (node (ref "U5") (pin "GND@10") (pinfunction "PAD_GND@10") (pintype "bidirectional"))
      (node (ref "U5") (pin "GND@11") (pinfunction "PAD_GND@11") (pintype "bidirectional"))
      (node (ref "U5") (pin "GND@12") (pinfunction "PAD_GND@12") (pintype "bidirectional"))
      (node (ref "U5") (pin "GND@13") (pinfunction "PAD_GND@13") (pintype "bidirectional"))
      (node (ref "U5") (pin "GND@14") (pinfunction "PAD_GND@14") (pintype "bidirectional"))
      (node (ref "U5") (pin "GND@15") (pinfunction "PAD_GND@15") (pintype "bidirectional"))
      (node (ref "U5") (pin "GND@16") (pinfunction "PAD_GND@16") (pintype "bidirectional"))
      (node (ref "U5") (pin "GND@17") (pinfunction "PAD_GND@17") (pintype "bidirectional"))
      (node (ref "U5") (pin "GND@18") (pinfunction "PAD_GND@18") (pintype "bidirectional"))
      (node (ref "U5") (pin "GND@19") (pinfunction "PAD_GND@19") (pintype "bidirectional"))
      (node (ref "U5") (pin "GND@20") (pinfunction "PAD_GND@20") (pintype "bidirectional"))
      (node (ref "U5") (pin "GND@21") (pinfunction "PAD_GND@21") (pintype "bidirectional"))
      (node (ref "U5") (pin "GND@22") (pinfunction "PAD_GND@22") (pintype "bidirectional"))
      (node (ref "U5") (pin "GND@23") (pinfunction "PAD_GND@23") (pintype "bidirectional"))
      (node (ref "U5") (pin "GND@24") (pinfunction "PAD_GND@24") (pintype "bidirectional"))
      (node (ref "U5") (pin "GND@25") (pinfunction "PAD_GND@25") (pintype "bidirectional"))
      (node (ref "U5") (pin "GND@26") (pinfunction "PAD_GND@26") (pintype "bidirectional"))
      (node (ref "U5") (pin "GND@27") (pinfunction "PAD_GND@27") (pintype "bidirectional"))
      (node (ref "U5") (pin "GND@28") (pinfunction "PAD_GND@28") (pintype "bidirectional"))
      (node (ref "U5") (pin "GND@29") (pinfunction "PAD_GND@29") (pintype "bidirectional"))
      (node (ref "U5") (pin "GND@30") (pinfunction "PAD_GND@30") (pintype "bidirectional"))
      (node (ref "U5") (pin "GND@PAD") (pinfunction "PAD_GND@PAD") (pintype "bidirectional"))
      (node (ref "U6") (pin "7") (pinfunction "GND_7") (pintype "power_in"))
      (node (ref "U7") (pin "3") (pinfunction "GND_3") (pintype "bidirectional"))
      (node (ref "U8") (pin "16") (pinfunction "SRN_16") (pintype "bidirectional"))
      (node (ref "U8") (pin "21") (pinfunction "GND_21") (pintype "bidirectional"))
      (node (ref "U8") (pin "7") (pinfunction "GND_7") (pintype "bidirectional"))
      (node (ref "U8") (pin "GND@10") (pinfunction "PAD_GND@10") (pintype "bidirectional"))
      (node (ref "U8") (pin "GND@11") (pinfunction "PAD_GND@11") (pintype "bidirectional"))
      (node (ref "U8") (pin "GND@12") (pinfunction "PAD_GND@12") (pintype "bidirectional"))
      (node (ref "U8") (pin "GND@13") (pinfunction "PAD_GND@13") (pintype "bidirectional"))
      (node (ref "U8") (pin "GND@14") (pinfunction "PAD_GND@14") (pintype "bidirectional"))
      (node (ref "U8") (pin "GND@15") (pinfunction "PAD_GND@15") (pintype "bidirectional"))
      (node (ref "U8") (pin "GND@16") (pinfunction "PAD_GND@16") (pintype "bidirectional"))
      (node (ref "U8") (pin "GND@17") (pinfunction "PAD_GND@17") (pintype "bidirectional"))
      (node (ref "U8") (pin "GND@18") (pinfunction "PAD_GND@18") (pintype "bidirectional"))
      (node (ref "U8") (pin "GND@19") (pinfunction "PAD_GND@19") (pintype "bidirectional"))
      (node (ref "U8") (pin "GND@20") (pinfunction "PAD_GND@20") (pintype "bidirectional"))
      (node (ref "U8") (pin "GND@21") (pinfunction "PAD_GND@21") (pintype "bidirectional"))
      (node (ref "U8") (pin "GND@22") (pinfunction "PAD_GND@22") (pintype "bidirectional"))
      (node (ref "U8") (pin "GND@23") (pinfunction "PAD_GND@23") (pintype "bidirectional"))
      (node (ref "U8") (pin "GND@24") (pinfunction "PAD_GND@24") (pintype "bidirectional"))
      (node (ref "U8") (pin "GND@25") (pinfunction "PAD_GND@25") (pintype "bidirectional"))
      (node (ref "U8") (pin "GND@26") (pinfunction "PAD_GND@26") (pintype "bidirectional"))
      (node (ref "U8") (pin "GND@27") (pinfunction "PAD_GND@27") (pintype "bidirectional"))
      (node (ref "U8") (pin "GND@28") (pinfunction "PAD_GND@28") (pintype "bidirectional"))
      (node (ref "U8") (pin "GND@29") (pinfunction "PAD_GND@29") (pintype "bidirectional"))
      (node (ref "U8") (pin "GND@30") (pinfunction "PAD_GND@30") (pintype "bidirectional"))
      (node (ref "U8") (pin "GND@PAD") (pinfunction "PAD_GND@PAD") (pintype "bidirectional"))
      (node (ref "U9") (pin "16") (pinfunction "SRN_16") (pintype "bidirectional"))
      (node (ref "U9") (pin "21") (pinfunction "GND_21") (pintype "bidirectional"))
      (node (ref "U9") (pin "7") (pinfunction "GND_7") (pintype "bidirectional"))
      (node (ref "U9") (pin "GND@10") (pinfunction "PAD_GND@10") (pintype "bidirectional"))
      (node (ref "U9") (pin "GND@11") (pinfunction "PAD_GND@11") (pintype "bidirectional"))
      (node (ref "U9") (pin "GND@12") (pinfunction "PAD_GND@12") (pintype "bidirectional"))
      (node (ref "U9") (pin "GND@13") (pinfunction "PAD_GND@13") (pintype "bidirectional"))
      (node (ref "U9") (pin "GND@14") (pinfunction "PAD_GND@14") (pintype "bidirectional"))
      (node (ref "U9") (pin "GND@15") (pinfunction "PAD_GND@15") (pintype "bidirectional"))
      (node (ref "U9") (pin "GND@16") (pinfunction "PAD_GND@16") (pintype "bidirectional"))
      (node (ref "U9") (pin "GND@17") (pinfunction "PAD_GND@17") (pintype "bidirectional"))
      (node (ref "U9") (pin "GND@18") (pinfunction "PAD_GND@18") (pintype "bidirectional"))
      (node (ref "U9") (pin "GND@19") (pinfunction "PAD_GND@19") (pintype "bidirectional"))
      (node (ref "U9") (pin "GND@20") (pinfunction "PAD_GND@20") (pintype "bidirectional"))
      (node (ref "U9") (pin "GND@21") (pinfunction "PAD_GND@21") (pintype "bidirectional"))
      (node (ref "U9") (pin "GND@22") (pinfunction "PAD_GND@22") (pintype "bidirectional"))
      (node (ref "U9") (pin "GND@23") (pinfunction "PAD_GND@23") (pintype "bidirectional"))
      (node (ref "U9") (pin "GND@24") (pinfunction "PAD_GND@24") (pintype "bidirectional"))
      (node (ref "U9") (pin "GND@25") (pinfunction "PAD_GND@25") (pintype "bidirectional"))
      (node (ref "U9") (pin "GND@26") (pinfunction "PAD_GND@26") (pintype "bidirectional"))
      (node (ref "U9") (pin "GND@27") (pinfunction "PAD_GND@27") (pintype "bidirectional"))
      (node (ref "U9") (pin "GND@28") (pinfunction "PAD_GND@28") (pintype "bidirectional"))
      (node (ref "U9") (pin "GND@29") (pinfunction "PAD_GND@29") (pintype "bidirectional"))
      (node (ref "U9") (pin "GND@30") (pinfunction "PAD_GND@30") (pintype "bidirectional"))
      (node (ref "U9") (pin "GND@PAD") (pinfunction "PAD_GND@PAD") (pintype "bidirectional"))
    )
    (net (code "23") (name "MISO-D12-LIMIT-Z") (class "Default")
      (node (ref "J1") (pin "1") (pinfunction "1_1") (pintype "passive"))
      (node (ref "U1") (pin "16") (pinfunction "PB4(MISO)_16") (pintype "bidirectional"))
      (node (ref "U6") (pin "6") (pinfunction "3Y_6") (pintype "output"))
    )
    (net (code "24") (name "MOSI-D11-SPINDLE_PWM") (class "Default")
      (node (ref "J1") (pin "4") (pinfunction "4_4") (pintype "passive"))
      (node (ref "U1") (pin "15") (pinfunction "PB3(MOSI/OC2)_15") (pintype "bidirectional"))
    )
    (net (code "25") (name "Net-(D1-PadA)") (class "Default")
      (node (ref "D1") (pin "A") (pinfunction "A_A") (pintype "passive"))
      (node (ref "R18") (pin "1") (pinfunction "1_1") (pintype "passive"))
    )
    (net (code "26") (name "Net-(D2-PadA)") (class "Default")
      (node (ref "D2") (pin "A") (pinfunction "A_A") (pintype "passive"))
      (node (ref "R9") (pin "1") (pinfunction "1_1") (pintype "passive"))
    )
    (net (code "27") (name "Net-(D4-PadA)") (class "Default")
      (node (ref "D4") (pin "A") (pinfunction "A_A") (pintype "passive"))
      (node (ref "R39") (pin "1") (pinfunction "1_1") (pintype "passive"))
    )
    (net (code "28") (name "Net-(D5-PadA)") (class "Default")
      (node (ref "D5") (pin "A") (pinfunction "A_A") (pintype "passive"))
      (node (ref "R32") (pin "1") (pinfunction "1_1") (pintype "passive"))
    )
    (net (code "29") (name "Net-(D6-PadA)") (class "Default")
      (node (ref "D6") (pin "A") (pinfunction "A_A") (pintype "passive"))
      (node (ref "R31") (pin "1") (pinfunction "1_1") (pintype "passive"))
    )
    (net (code "30") (name "Net-(D7-PadA)") (class "Default")
      (node (ref "D7") (pin "A") (pinfunction "A_A") (pintype "passive"))
      (node (ref "R40") (pin "1") (pinfunction "1_1") (pintype "passive"))
    )
    (net (code "31") (name "Net-(D8-PadA)") (class "Default")
      (node (ref "D8") (pin "A") (pinfunction "A_A") (pintype "passive"))
      (node (ref "R43") (pin "1") (pinfunction "1_1") (pintype "passive"))
    )
    (net (code "32") (name "Net-(D9-PadA)") (class "Default")
      (node (ref "D9") (pin "A") (pinfunction "A_A") (pintype "passive"))
      (node (ref "R42") (pin "1") (pinfunction "1_1") (pintype "passive"))
    )
    (net (code "33") (name "Net-(D10-PadA)") (class "Default")
      (node (ref "D10") (pin "A") (pinfunction "A_A") (pintype "passive"))
      (node (ref "R41") (pin "1") (pinfunction "1_1") (pintype "passive"))
    )
    (net (code "34") (name "Net-(D11-PadA)") (class "Default")
      (node (ref "D11") (pin "A") (pinfunction "A_A") (pintype "passive"))
      (node (ref "R44") (pin "1") (pinfunction "1_1") (pintype "passive"))
    )
    (net (code "35") (name "Net-(D12-PadA)") (class "Default")
      (node (ref "D12") (pin "A") (pinfunction "A_A") (pintype "passive"))
      (node (ref "R47") (pin "1") (pinfunction "1_1") (pintype "passive"))
    )
    (net (code "36") (name "Net-(D13-PadA)") (class "Default")
      (node (ref "D13") (pin "A") (pinfunction "A_A") (pintype "passive"))
      (node (ref "R46") (pin "1") (pinfunction "1_1") (pintype "passive"))
    )
    (net (code "37") (name "Net-(D14-PadA)") (class "Default")
      (node (ref "D14") (pin "A") (pinfunction "A_A") (pintype "passive"))
      (node (ref "R45") (pin "1") (pinfunction "1_1") (pintype "passive"))
    )
    (net (code "38") (name "Net-(D15-PadA)") (class "Default")
      (node (ref "D15") (pin "A") (pinfunction "A_A") (pintype "passive"))
      (node (ref "R49") (pin "1") (pinfunction "1_1") (pintype "passive"))
    )
    (net (code "39") (name "Net-(D16-PadA)") (class "Default")
      (node (ref "D16") (pin "A") (pinfunction "A_A") (pintype "passive"))
      (node (ref "F1") (pin "2") (pinfunction "2_2") (pintype "bidirectional"))
    )
    (net (code "40") (name "Net-(JP1-Pad2)") (class "Default")
      (node (ref "JP1") (pin "2") (pinfunction "2_2") (pintype "passive"))
      (node (ref "R30") (pin "1") (pinfunction "1_1") (pintype "passive"))
      (node (ref "R38") (pin "2") (pinfunction "2_2") (pintype "passive"))
    )
    (net (code "41") (name "Net-(JP3-Pad2)") (class "Default")
      (node (ref "JP3") (pin "2") (pinfunction "2_2") (pintype "passive"))
      (node (ref "R27") (pin "2") (pinfunction "2_2") (pintype "passive"))
      (node (ref "R33") (pin "1") (pinfunction "1_1") (pintype "passive"))
    )
    (net (code "42") (name "Net-(JP4-Pad2)") (class "Default")
      (node (ref "JP4") (pin "2") (pinfunction "2_2") (pintype "passive"))
      (node (ref "R28") (pin "2") (pinfunction "2_2") (pintype "passive"))
      (node (ref "R34") (pin "1") (pinfunction "1_1") (pintype "passive"))
    )
    (net (code "43") (name "Net-(JP8-Pad2)") (class "Default")
      (node (ref "JP8") (pin "2") (pinfunction "2_2") (pintype "passive"))
      (node (ref "R29") (pin "2") (pinfunction "2_2") (pintype "passive"))
      (node (ref "R36") (pin "1") (pinfunction "1_1") (pintype "passive"))
    )
    (net (code "44") (name "Net-(JP9-Pad2)") (class "Default")
      (node (ref "JP9") (pin "2") (pinfunction "2_2") (pintype "passive"))
      (node (ref "R35") (pin "2") (pinfunction "2_2") (pintype "passive"))
      (node (ref "R48") (pin "1") (pinfunction "1_1") (pintype "passive"))
    )
    (net (code "45") (name "Net-(L1-1)") (class "Default")
      (node (ref "C7") (pin "2") (pinfunction "2_2") (pintype "passive"))
      (node (ref "D17") (pin "C") (pinfunction "C_C") (pintype "passive"))
      (node (ref "L1") (pin "P$1") (pinfunction "1_P$1") (pintype "passive"))
      (node (ref "U4") (pin "9") (pinfunction "SW_9") (pintype "bidirectional"))
    )
    (net (code "46") (name "Net-(POT1-A)") (class "Default")
      (node (ref "POT1") (pin "1") (pinfunction "A_1") (pintype "passive"))
      (node (ref "R1") (pin "2") (pinfunction "2_2") (pintype "passive"))
    )
    (net (code "47") (name "Net-(POT1-E)") (class "Default")
      (node (ref "POT1") (pin "3") (pinfunction "E_3") (pintype "passive"))
      (node (ref "R37") (pin "1") (pinfunction "1_1") (pintype "passive"))
    )
    (net (code "48") (name "Net-(POT1-S)") (class "Default")
      (node (ref "POT1") (pin "2") (pinfunction "S_2") (pintype "passive"))
      (node (ref "U5") (pin "8") (pinfunction "VREF_8") (pintype "bidirectional"))
    )
    (net (code "49") (name "Net-(POT2-A)") (class "Default")
      (node (ref "POT2") (pin "1") (pinfunction "A_1") (pintype "passive"))
      (node (ref "R17") (pin "2") (pinfunction "2_2") (pintype "passive"))
    )
    (net (code "50") (name "Net-(POT2-E)") (class "Default")
      (node (ref "POT2") (pin "3") (pinfunction "E_3") (pintype "passive"))
      (node (ref "R16") (pin "1") (pinfunction "1_1") (pintype "passive"))
    )
    (net (code "51") (name "Net-(POT2-S)") (class "Default")
      (node (ref "POT2") (pin "2") (pinfunction "S_2") (pintype "passive"))
      (node (ref "U8") (pin "8") (pinfunction "VREF_8") (pintype "bidirectional"))
    )
    (net (code "52") (name "Net-(POT3-A)") (class "Default")
      (node (ref "POT3") (pin "1") (pinfunction "A_1") (pintype "passive"))
      (node (ref "R26") (pin "2") (pinfunction "2_2") (pintype "passive"))
    )
    (net (code "53") (name "Net-(POT3-E)") (class "Default")
      (node (ref "POT3") (pin "3") (pinfunction "E_3") (pintype "passive"))
      (node (ref "R25") (pin "1") (pinfunction "1_1") (pintype "passive"))
    )
    (net (code "54") (name "Net-(POT3-S)") (class "Default")
      (node (ref "POT3") (pin "2") (pinfunction "S_2") (pintype "passive"))
      (node (ref "U9") (pin "8") (pinfunction "VREF_8") (pintype "bidirectional"))
    )
    (net (code "55") (name "Net-(POWER-PadA)") (class "Default")
      (node (ref "POWER") (pin "A") (pinfunction "A_A") (pintype "passive"))
      (node (ref "R56") (pin "2") (pinfunction "2_2") (pintype "passive"))
    )
    (net (code "56") (name "Net-(PROTECT-PadC)") (class "Default")
      (node (ref "PROTECT") (pin "C") (pinfunction "C_C") (pintype "passive"))
      (node (ref "R51") (pin "2") (pinfunction "2_2") (pintype "passive"))
    )
    (net (code "57") (name "Net-(Q2-D)") (class "Default")
      (node (ref "C2") (pin "1") (pinfunction "1_1") (pintype "passive"))
      (node (ref "JP6") (pin "GND") (pinfunction "GND_GND") (pintype "bidirectional"))
      (node (ref "PROTECT") (pin "A") (pinfunction "A_A") (pintype "passive"))
      (node (ref "Q2") (pin "2") (pinfunction "D_2") (pintype "passive"))
      (node (ref "VIN") (pin "1") (pinfunction "1_1") (pintype "passive"))
    )
    (net (code "58") (name "Net-(Q2-G)") (class "Default")
      (node (ref "Q2") (pin "1") (pinfunction "G_1") (pintype "passive"))
      (node (ref "R50") (pin "2") (pinfunction "2_2") (pintype "passive"))
    )
    (net (code "59") (name "Net-(R27-Pad1)") (class "Default")
      (node (ref "R27") (pin "1") (pinfunction "1_1") (pintype "passive"))
      (node (ref "R28") (pin "1") (pinfunction "1_1") (pintype "passive"))
      (node (ref "R38") (pin "1") (pinfunction "1_1") (pintype "passive"))
      (node (ref "SJ1") (pin "2") (pinfunction "2_2") (pintype "passive"))
    )
    (net (code "60") (name "Net-(S1-P$1)") (class "Default")
      (node (ref "S1") (pin "1") (pinfunction "P$1_1") (pintype "bidirectional"))
      (node (ref "U5") (pin "12") (pinfunction "USM1_12") (pintype "bidirectional"))
    )
    (net (code "61") (name "Net-(S1-P$2)") (class "Default")
      (node (ref "S1") (pin "2") (pinfunction "P$2_2") (pintype "bidirectional"))
      (node (ref "U5") (pin "13") (pinfunction "USM0_13") (pintype "bidirectional"))
    )
    (net (code "62") (name "Net-(S2-P$1)") (class "Default")
      (node (ref "S2") (pin "1") (pinfunction "P$1_1") (pintype "bidirectional"))
      (node (ref "U8") (pin "12") (pinfunction "USM1_12") (pintype "bidirectional"))
    )
    (net (code "63") (name "Net-(S2-P$2)") (class "Default")
      (node (ref "S2") (pin "2") (pinfunction "P$2_2") (pintype "bidirectional"))
      (node (ref "U8") (pin "13") (pinfunction "USM0_13") (pintype "bidirectional"))
    )
    (net (code "64") (name "Net-(S3-P$1)") (class "Default")
      (node (ref "S3") (pin "1") (pinfunction "P$1_1") (pintype "bidirectional"))
      (node (ref "U9") (pin "12") (pinfunction "USM1_12") (pintype "bidirectional"))
    )
    (net (code "65") (name "Net-(S3-P$2)") (class "Default")
      (node (ref "S3") (pin "2") (pinfunction "P$2_2") (pintype "bidirectional"))
      (node (ref "U9") (pin "13") (pinfunction "USM0_13") (pintype "bidirectional"))
    )
    (net (code "66") (name "Net-(U1-PB6(XTAL1{slash}TOSC1))") (class "Default")
      (node (ref "Q1") (pin "1") (pinfunction "1_1") (pintype "passive"))
      (node (ref "U1") (pin "7") (pinfunction "PB6(XTAL1/TOSC1)_7") (pintype "bidirectional"))
    )
    (net (code "67") (name "Net-(U1-PB7(XTAL2{slash}TOSC2))") (class "Default")
      (node (ref "Q1") (pin "3") (pinfunction "3_3") (pintype "passive"))
      (node (ref "U1") (pin "8") (pinfunction "PB7(XTAL2/TOSC2)_8") (pintype "bidirectional"))
    )
    (net (code "68") (name "Net-(U2-RXLED)") (class "Default")
      (node (ref "D2") (pin "C") (pinfunction "C_C") (pintype "passive"))
      (node (ref "U2") (pin "22") (pinfunction "RXLED_22") (pintype "input"))
    )
    (net (code "69") (name "Net-(U2-TXLED)") (class "Default")
      (node (ref "D1") (pin "C") (pinfunction "C_C") (pintype "passive"))
      (node (ref "U2") (pin "23") (pinfunction "TXLED_23") (pintype "input"))
    )
    (net (code "70") (name "Net-(U2-USBDM)") (class "Default")
      (node (ref "JP5") (pin "D-") (pinfunction "D-_D-") (pintype "bidirectional"))
      (node (ref "U2") (pin "16") (pinfunction "USBDM_16") (pintype "bidirectional"))
    )
    (net (code "71") (name "Net-(U2-USBDP)") (class "Default")
      (node (ref "JP5") (pin "D+") (pinfunction "D+_D+") (pintype "bidirectional"))
      (node (ref "U2") (pin "15") (pinfunction "USBDP_15") (pintype "bidirectional"))
    )
    (net (code "72") (name "Net-(U3-A)") (class "Default")
      (node (ref "U3") (pin "2") (pinfunction "A_2") (pintype "bidirectional"))
      (node (ref "U6") (pin "10") (pinfunction "5Y_10") (pintype "output"))
    )
    (net (code "73") (name "Net-(U3-Y)") (class "Default")
      (node (ref "U3") (pin "4") (pinfunction "Y_4") (pintype "bidirectional"))
      (node (ref "U7") (pin "2") (pinfunction "B_2") (pintype "bidirectional"))
    )
    (net (code "74") (name "Net-(U4-BST)") (class "Default")
      (node (ref "C7") (pin "1") (pinfunction "1_1") (pintype "passive"))
      (node (ref "U4") (pin "10") (pinfunction "BST_10") (pintype "bidirectional"))
    )
    (net (code "75") (name "Net-(U4-CS)") (class "Default")
      (node (ref "D17") (pin "A") (pinfunction "A_A") (pintype "passive"))
      (node (ref "R54") (pin "2") (pinfunction "2_2") (pintype "passive"))
      (node (ref "U4") (pin "8") (pinfunction "CS_8") (pintype "bidirectional"))
    )
    (net (code "76") (name "Net-(U4-FB)") (class "Default")
      (node (ref "R52") (pin "1") (pinfunction "1_1") (pintype "passive"))
      (node (ref "R53") (pin "1") (pinfunction "1_1") (pintype "passive"))
      (node (ref "U4") (pin "6") (pinfunction "FB_6") (pintype "bidirectional"))
    )
    (net (code "77") (name "Net-(U4-RT)") (class "Default")
      (node (ref "R55") (pin "1") (pinfunction "1_1") (pintype "passive"))
      (node (ref "U4") (pin "2") (pinfunction "RT_2") (pintype "bidirectional"))
    )
    (net (code "78") (name "Net-(U4-SS)") (class "Default")
      (node (ref "C9") (pin "1") (pinfunction "1_1") (pintype "passive"))
      (node (ref "U4") (pin "4") (pinfunction "SS_4") (pintype "bidirectional"))
    )
    (net (code "79") (name "Net-(U5-AOUT1)") (class "Default")
      (node (ref "U5") (pin "4") (pinfunction "AOUT1_4") (pintype "bidirectional"))
      (node (ref "X-A") (pin "1") (pinfunction "1_1") (pintype "passive"))
    )
    (net (code "80") (name "Net-(U5-AOUT2)") (class "Default")
      (node (ref "U5") (pin "25") (pinfunction "AOUT2_25") (pintype "bidirectional"))
      (node (ref "X-A") (pin "2") (pinfunction "2_2") (pintype "passive"))
    )
    (net (code "81") (name "Net-(U5-BOUT1)") (class "Default")
      (node (ref "U5") (pin "11") (pinfunction "BOUT1_11") (pintype "bidirectional"))
      (node (ref "X-B") (pin "1") (pinfunction "1_1") (pintype "passive"))
    )
    (net (code "82") (name "Net-(U5-BOUT2)") (class "Default")
      (node (ref "U5") (pin "18") (pinfunction "BOUT2_18") (pintype "bidirectional"))
      (node (ref "X-B") (pin "2") (pinfunction "2_2") (pintype "passive"))
    )
    (net (code "83") (name "Net-(U5-CP1)") (class "Default")
      (node (ref "C16") (pin "2") (pinfunction "2_2") (pintype "passive"))
      (node (ref "U5") (pin "23") (pinfunction "CP1_23") (pintype "bidirectional"))
    )
    (net (code "84") (name "Net-(U5-CP2)") (class "Default")
      (node (ref "C16") (pin "1") (pinfunction "1_1") (pintype "passive"))
      (node (ref "U5") (pin "24") (pinfunction "CP2_24") (pintype "bidirectional"))
    )
    (net (code "85") (name "Net-(U5-DECAY)") (class "Default")
      (node (ref "C32") (pin "1") (pinfunction "1_1") (pintype "passive"))
      (node (ref "R14") (pin "1") (pinfunction "1_1") (pintype "passive"))
      (node (ref "R15") (pin "2") (pinfunction "2_2") (pintype "passive"))
      (node (ref "U5") (pin "5") (pinfunction "DECAY_5") (pintype "bidirectional"))
    )
    (net (code "86") (name "Net-(U5-ISENA)") (class "Default")
      (node (ref "C20") (pin "1") (pinfunction "1_1") (pintype "passive"))
      (node (ref "R10") (pin "2") (pinfunction "2_2") (pintype "passive"))
      (node (ref "U5") (pin "1") (pinfunction "ISENA_1") (pintype "bidirectional"))
    )
    (net (code "87") (name "Net-(U5-ISENB)") (class "Default")
      (node (ref "C19") (pin "1") (pinfunction "1_1") (pintype "passive"))
      (node (ref "R11") (pin "2") (pinfunction "2_2") (pintype "passive"))
      (node (ref "U5") (pin "14") (pinfunction "ISENB_14") (pintype "bidirectional"))
    )
    (net (code "88") (name "Net-(U5-RCA)") (class "Default")
      (node (ref "C21") (pin "1") (pinfunction "1_1") (pintype "passive"))
      (node (ref "R12") (pin "2") (pinfunction "2_2") (pintype "passive"))
      (node (ref "U5") (pin "6") (pinfunction "RCA_6") (pintype "bidirectional"))
    )
    (net (code "89") (name "Net-(U5-RCB)") (class "Default")
      (node (ref "C22") (pin "1") (pinfunction "1_1") (pintype "passive"))
      (node (ref "R13") (pin "2") (pinfunction "2_2") (pintype "passive"))
      (node (ref "U5") (pin "9") (pinfunction "RCB_9") (pintype "bidirectional"))
    )
    (net (code "90") (name "Net-(U5-VCP)") (class "Default")
      (node (ref "C17") (pin "2") (pinfunction "2_2") (pintype "passive"))
      (node (ref "U5") (pin "22") (pinfunction "VCP_22") (pintype "bidirectional"))
    )
    (net (code "91") (name "Net-(U5-VGD)") (class "Default")
      (node (ref "C18") (pin "2") (pinfunction "2_2") (pintype "passive"))
      (node (ref "U5") (pin "20") (pinfunction "VGD_20") (pintype "bidirectional"))
    )
    (net (code "92") (name "Net-(U8-AOUT1)") (class "Default")
      (node (ref "U8") (pin "4") (pinfunction "AOUT1_4") (pintype "bidirectional"))
      (node (ref "Y-A") (pin "1") (pinfunction "1_1") (pintype "passive"))
    )
    (net (code "93") (name "Net-(U8-AOUT2)") (class "Default")
      (node (ref "U8") (pin "25") (pinfunction "AOUT2_25") (pintype "bidirectional"))
      (node (ref "Y-A") (pin "2") (pinfunction "2_2") (pintype "passive"))
    )
    (net (code "94") (name "Net-(U8-BOUT1)") (class "Default")
      (node (ref "U8") (pin "11") (pinfunction "BOUT1_11") (pintype "bidirectional"))
      (node (ref "Y-B") (pin "1") (pinfunction "1_1") (pintype "passive"))
    )
    (net (code "95") (name "Net-(U8-BOUT2)") (class "Default")
      (node (ref "U8") (pin "18") (pinfunction "BOUT2_18") (pintype "bidirectional"))
      (node (ref "Y-B") (pin "2") (pinfunction "2_2") (pintype "passive"))
    )
    (net (code "96") (name "Net-(U8-CP1)") (class "Default")
      (node (ref "C1") (pin "2") (pinfunction "2_2") (pintype "passive"))
      (node (ref "U8") (pin "23") (pinfunction "CP1_23") (pintype "bidirectional"))
    )
    (net (code "97") (name "Net-(U8-CP2)") (class "Default")
      (node (ref "C1") (pin "1") (pinfunction "1_1") (pintype "passive"))
      (node (ref "U8") (pin "24") (pinfunction "CP2_24") (pintype "bidirectional"))
    )
    (net (code "98") (name "Net-(U8-DECAY)") (class "Default")
      (node (ref "C15") (pin "1") (pinfunction "1_1") (pintype "passive"))
      (node (ref "R7") (pin "1") (pinfunction "1_1") (pintype "passive"))
      (node (ref "R8") (pin "2") (pinfunction "2_2") (pintype "passive"))
      (node (ref "U8") (pin "5") (pinfunction "DECAY_5") (pintype "bidirectional"))
    )
    (net (code "99") (name "Net-(U8-ISENA)") (class "Default")
      (node (ref "C11") (pin "1") (pinfunction "1_1") (pintype "passive"))
      (node (ref "R2") (pin "2") (pinfunction "2_2") (pintype "passive"))
      (node (ref "U8") (pin "1") (pinfunction "ISENA_1") (pintype "bidirectional"))
    )
    (net (code "100") (name "Net-(U8-ISENB)") (class "Default")
      (node (ref "C10") (pin "1") (pinfunction "1_1") (pintype "passive"))
      (node (ref "R3") (pin "2") (pinfunction "2_2") (pintype "passive"))
      (node (ref "U8") (pin "14") (pinfunction "ISENB_14") (pintype "bidirectional"))
    )
    (net (code "101") (name "Net-(U8-RCA)") (class "Default")
      (node (ref "C12") (pin "1") (pinfunction "1_1") (pintype "passive"))
      (node (ref "R4") (pin "2") (pinfunction "2_2") (pintype "passive"))
      (node (ref "U8") (pin "6") (pinfunction "RCA_6") (pintype "bidirectional"))
    )
    (net (code "102") (name "Net-(U8-RCB)") (class "Default")
      (node (ref "C13") (pin "1") (pinfunction "1_1") (pintype "passive"))
      (node (ref "R5") (pin "2") (pinfunction "2_2") (pintype "passive"))
      (node (ref "U8") (pin "9") (pinfunction "RCB_9") (pintype "bidirectional"))
    )
    (net (code "103") (name "Net-(U8-VCP)") (class "Default")
      (node (ref "C6") (pin "2") (pinfunction "2_2") (pintype "passive"))
      (node (ref "U8") (pin "22") (pinfunction "VCP_22") (pintype "bidirectional"))
    )
    (net (code "104") (name "Net-(U8-VGD)") (class "Default")
      (node (ref "C8") (pin "2") (pinfunction "2_2") (pintype "passive"))
      (node (ref "U8") (pin "20") (pinfunction "VGD_20") (pintype "bidirectional"))
    )
    (net (code "105") (name "Net-(U9-AOUT1)") (class "Default")
      (node (ref "U9") (pin "4") (pinfunction "AOUT1_4") (pintype "bidirectional"))
      (node (ref "Z-A") (pin "1") (pinfunction "1_1") (pintype "passive"))
    )
    (net (code "106") (name "Net-(U9-AOUT2)") (class "Default")
      (node (ref "U9") (pin "25") (pinfunction "AOUT2_25") (pintype "bidirectional"))
      (node (ref "Z-A") (pin "2") (pinfunction "2_2") (pintype "passive"))
    )
    (net (code "107") (name "Net-(U9-BOUT1)") (class "Default")
      (node (ref "U9") (pin "11") (pinfunction "BOUT1_11") (pintype "bidirectional"))
      (node (ref "Z-B") (pin "1") (pinfunction "1_1") (pintype "passive"))
    )
    (net (code "108") (name "Net-(U9-BOUT2)") (class "Default")
      (node (ref "U9") (pin "18") (pinfunction "BOUT2_18") (pintype "bidirectional"))
      (node (ref "Z-B") (pin "2") (pinfunction "2_2") (pintype "passive"))
    )
    (net (code "109") (name "Net-(U9-CP1)") (class "Default")
      (node (ref "C27") (pin "2") (pinfunction "2_2") (pintype "passive"))
      (node (ref "U9") (pin "23") (pinfunction "CP1_23") (pintype "bidirectional"))
    )
    (net (code "110") (name "Net-(U9-CP2)") (class "Default")
      (node (ref "C27") (pin "1") (pinfunction "1_1") (pintype "passive"))
      (node (ref "U9") (pin "24") (pinfunction "CP2_24") (pintype "bidirectional"))
    )
    (net (code "111") (name "Net-(U9-DECAY)") (class "Default")
      (node (ref "C36") (pin "1") (pinfunction "1_1") (pintype "passive"))
      (node (ref "R23") (pin "1") (pinfunction "1_1") (pintype "passive"))
      (node (ref "R24") (pin "2") (pinfunction "2_2") (pintype "passive"))
      (node (ref "U9") (pin "5") (pinfunction "DECAY_5") (pintype "bidirectional"))
    )
    (net (code "112") (name "Net-(U9-ISENA)") (class "Default")
      (node (ref "C31") (pin "1") (pinfunction "1_1") (pintype "passive"))
      (node (ref "R19") (pin "2") (pinfunction "2_2") (pintype "passive"))
      (node (ref "U9") (pin "1") (pinfunction "ISENA_1") (pintype "bidirectional"))
    )
    (net (code "113") (name "Net-(U9-ISENB)") (class "Default")
      (node (ref "C30") (pin "1") (pinfunction "1_1") (pintype "passive"))
      (node (ref "R20") (pin "2") (pinfunction "2_2") (pintype "passive"))
      (node (ref "U9") (pin "14") (pinfunction "ISENB_14") (pintype "bidirectional"))
    )
    (net (code "114") (name "Net-(U9-RCA)") (class "Default")
      (node (ref "C33") (pin "1") (pinfunction "1_1") (pintype "passive"))
      (node (ref "R21") (pin "2") (pinfunction "2_2") (pintype "passive"))
      (node (ref "U9") (pin "6") (pinfunction "RCA_6") (pintype "bidirectional"))
    )
    (net (code "115") (name "Net-(U9-RCB)") (class "Default")
      (node (ref "C34") (pin "1") (pinfunction "1_1") (pintype "passive"))
      (node (ref "R22") (pin "2") (pinfunction "2_2") (pintype "passive"))
      (node (ref "U9") (pin "9") (pinfunction "RCB_9") (pintype "bidirectional"))
    )
    (net (code "116") (name "Net-(U9-VCP)") (class "Default")
      (node (ref "C28") (pin "2") (pinfunction "2_2") (pintype "passive"))
      (node (ref "U9") (pin "22") (pinfunction "VCP_22") (pintype "bidirectional"))
    )
    (net (code "117") (name "Net-(U9-VGD)") (class "Default")
      (node (ref "C29") (pin "2") (pinfunction "2_2") (pintype "passive"))
      (node (ref "U9") (pin "20") (pinfunction "VGD_20") (pintype "bidirectional"))
    )
    (net (code "118") (name "PROBE") (class "Default")
      (node (ref "C57") (pin "1") (pinfunction "1_1") (pintype "passive"))
      (node (ref "D11") (pin "C") (pinfunction "C_C") (pintype "passive"))
      (node (ref "R36") (pin "2") (pinfunction "2_2") (pintype "passive"))
      (node (ref "U6") (pin "9") (pinfunction "4A_9") (pintype "input"))
    )
    (net (code "119") (name "RESET") (class "Default")
      (node (ref "C52") (pin "1") (pinfunction "1_1") (pintype "passive"))
      (node (ref "J1") (pin "5") (pinfunction "5_5") (pintype "passive"))
      (node (ref "JP17") (pin "6") (pinfunction "6_6") (pintype "passive"))
      (node (ref "R6") (pin "1") (pinfunction "1_1") (pintype "passive"))
      (node (ref "S4") (pin "3") (pinfunction "2_3") (pintype "passive"))
      (node (ref "U1") (pin "29") (pinfunction "PC6(/RESET)_29") (pintype "bidirectional"))
    )
    (net (code "120") (name "RXI") (class "Default")
      (node (ref "JP17") (pin "9") (pinfunction "9_9") (pintype "passive"))
      (node (ref "U1") (pin "30") (pinfunction "PD0(RXD)_30") (pintype "bidirectional"))
      (node (ref "U2") (pin "1") (pinfunction "TXD_1") (pintype "output"))
    )
    (net (code "121") (name "SCK-D13-SPINDLE_DIR") (class "Default")
      (node (ref "J1") (pin "3") (pinfunction "3_3") (pintype "passive"))
      (node (ref "U1") (pin "17") (pinfunction "PB5(SCK)_17") (pintype "bidirectional"))
    )
    (net (code "122") (name "STEP_ENABLE") (class "Default")
      (node (ref "JP19") (pin "6") (pinfunction "6_6") (pintype "passive"))
      (node (ref "R49") (pin "2") (pinfunction "2_2") (pintype "passive"))
      (node (ref "U5") (pin "26") (pinfunction "ENABLEN_26") (pintype "bidirectional"))
      (node (ref "U7") (pin "4") (pinfunction "Y_4") (pintype "bidirectional"))
      (node (ref "U8") (pin "26") (pinfunction "ENABLEN_26") (pintype "bidirectional"))
      (node (ref "U9") (pin "26") (pinfunction "ENABLEN_26") (pintype "bidirectional"))
    )
    (net (code "123") (name "TXO") (class "Default")
      (node (ref "JP17") (pin "10") (pinfunction "10_10") (pintype "passive"))
      (node (ref "U1") (pin "31") (pinfunction "PD1(TXD)_31") (pintype "bidirectional"))
      (node (ref "U2") (pin "5") (pinfunction "RXD_5") (pintype "input"))
    )
    (net (code "124") (name "VCC") (class "Default")
      (node (ref "C42") (pin "1") (pinfunction "1_1") (pintype "passive"))
      (node (ref "JP15") (pin "2") (pinfunction "2_2") (pintype "passive"))
      (node (ref "JP16") (pin "5") (pinfunction "5_5") (pintype "passive"))
      (node (ref "JP16") (pin "7") (pinfunction "7_7") (pintype "passive"))
      (node (ref "U10") (pin "2") (pinfunction "OUT_2") (pintype "output"))
    )
    (net (code "125") (name "VCC_USB") (class "Default")
      (node (ref "C53") (pin "1") (pinfunction "1_1") (pintype "passive"))
      (node (ref "F1") (pin "1") (pinfunction "1_1") (pintype "bidirectional"))
      (node (ref "JP5") (pin "VBUS") (pinfunction "VBUS_VBUS") (pintype "bidirectional"))
      (node (ref "U2") (pin "20") (pinfunction "VCC_20") (pintype "power_in"))
      (node (ref "U2") (pin "4") (pinfunction "VCCIO_4") (pintype "power_in"))
    )
    (net (code "126") (name "VIN") (class "Default")
      (node (ref "C14") (pin "+") (pinfunction "+_+") (pintype "passive"))
      (node (ref "C17") (pin "1") (pinfunction "1_1") (pintype "passive"))
      (node (ref "C2") (pin "2") (pinfunction "2_2") (pintype "passive"))
      (node (ref "C23") (pin "+") (pinfunction "+_+") (pintype "passive"))
      (node (ref "C25") (pin "+") (pinfunction "+_+") (pintype "passive"))
      (node (ref "C26") (pin "+") (pinfunction "+_+") (pintype "passive"))
      (node (ref "C28") (pin "1") (pinfunction "1_1") (pintype "passive"))
      (node (ref "C35") (pin "+") (pinfunction "+_+") (pintype "passive"))
      (node (ref "C38") (pin "+") (pinfunction "+_+") (pintype "passive"))
      (node (ref "C4") (pin "1") (pinfunction "1_1") (pintype "passive"))
      (node (ref "C41") (pin "+") (pinfunction "+_+") (pintype "passive"))
      (node (ref "C6") (pin "1") (pinfunction "1_1") (pintype "passive"))
      (node (ref "JP16") (pin "1") (pinfunction "1_1") (pintype "passive"))
      (node (ref "JP16") (pin "3") (pinfunction "3_3") (pintype "passive"))
      (node (ref "JP19") (pin "4") (pinfunction "4_4") (pintype "passive"))
      (node (ref "JP19") (pin "5") (pinfunction "5_5") (pintype "passive"))
      (node (ref "JP6") (pin "PWR") (pinfunction "PWR_PWR") (pintype "bidirectional"))
      (node (ref "R50") (pin "1") (pinfunction "1_1") (pintype "passive"))
      (node (ref "R51") (pin "1") (pinfunction "1_1") (pintype "passive"))
      (node (ref "R55") (pin "2") (pinfunction "2_2") (pintype "passive"))
      (node (ref "R56") (pin "1") (pinfunction "1_1") (pintype "passive"))
      (node (ref "U10") (pin "1") (pinfunction "IN_1") (pintype "input"))
      (node (ref "U4") (pin "1") (pinfunction "VIN_1") (pintype "bidirectional"))
      (node (ref "U5") (pin "15") (pinfunction "VMB_15") (pintype "bidirectional"))
      (node (ref "U5") (pin "28") (pinfunction "VMA_28") (pintype "bidirectional"))
      (node (ref "U8") (pin "15") (pinfunction "VMB_15") (pintype "bidirectional"))
      (node (ref "U8") (pin "28") (pinfunction "VMA_28") (pintype "bidirectional"))
      (node (ref "U9") (pin "15") (pinfunction "VMB_15") (pintype "bidirectional"))
      (node (ref "U9") (pin "28") (pinfunction "VMA_28") (pintype "bidirectional"))
      (node (ref "VIN") (pin "2") (pinfunction "2_2") (pintype "passive"))
    )
    (net (code "127") (name "X_LIM") (class "Default")
      (node (ref "C54") (pin "1") (pinfunction "1_1") (pintype "passive"))
      (node (ref "D6") (pin "C") (pinfunction "C_C") (pintype "passive"))
      (node (ref "R30") (pin "2") (pinfunction "2_2") (pintype "passive"))
      (node (ref "U6") (pin "1") (pinfunction "1A_1") (pintype "input"))
    )
    (net (code "128") (name "Y_LIM") (class "Default")
      (node (ref "C55") (pin "1") (pinfunction "1_1") (pintype "passive"))
      (node (ref "D10") (pin "C") (pinfunction "C_C") (pintype "passive"))
      (node (ref "R33") (pin "2") (pinfunction "2_2") (pintype "passive"))
      (node (ref "U6") (pin "3") (pinfunction "2A_3") (pintype "input"))
    )
    (net (code "129") (name "Z_LIM") (class "Default")
      (node (ref "C56") (pin "1") (pinfunction "1_1") (pintype "passive"))
      (node (ref "D14") (pin "C") (pinfunction "C_C") (pintype "passive"))
      (node (ref "R34") (pin "2") (pinfunction "2_2") (pintype "passive"))
      (node (ref "U6") (pin "5") (pinfunction "3A_5") (pintype "input"))
    )
    (net (code "130") (name "unconnected-(JP6-PadGNDBREAK)") (class "Default")
      (node (ref "JP6") (pin "GNDBREAK") (pinfunction "GNDBREAK_GNDBREAK") (pintype "bidirectional"))
    )
    (net (code "131") (name "unconnected-(U2-CTS-Pad11)") (class "Default")
      (node (ref "U2") (pin "11") (pinfunction "CTS_11") (pintype "input"))
    )
    (net (code "132") (name "unconnected-(U2-DCD-Pad10)") (class "Default")
      (node (ref "U2") (pin "10") (pinfunction "DCD_10") (pintype "input"))
    )
    (net (code "133") (name "unconnected-(U2-DSR-Pad9)") (class "Default")
      (node (ref "U2") (pin "9") (pinfunction "DSR_9") (pintype "input"))
    )
    (net (code "134") (name "unconnected-(U2-OSCI-Pad27)") (class "Default")
      (node (ref "U2") (pin "27") (pinfunction "OSCI_27") (pintype "input"))
    )
    (net (code "135") (name "unconnected-(U2-OSCO-Pad28)") (class "Default")
      (node (ref "U2") (pin "28") (pinfunction "OSCO_28") (pintype "output"))
    )
    (net (code "136") (name "unconnected-(U2-PWREN-Pad14)") (class "Default")
      (node (ref "U2") (pin "14") (pinfunction "PWREN_14") (pintype "input"))
    )
    (net (code "137") (name "unconnected-(U2-RESET-Pad19)") (class "Default")
      (node (ref "U2") (pin "19") (pinfunction "RESET_19") (pintype "input"))
    )
    (net (code "138") (name "unconnected-(U2-RI-Pad6)") (class "Default")
      (node (ref "U2") (pin "6") (pinfunction "RI_6") (pintype "input"))
    )
    (net (code "139") (name "unconnected-(U2-RTS-Pad3)") (class "Default")
      (node (ref "U2") (pin "3") (pinfunction "RTS_3") (pintype "output"))
    )
    (net (code "140") (name "unconnected-(U2-SLEEP-Pad12)") (class "Default")
      (node (ref "U2") (pin "12") (pinfunction "SLEEP_12") (pintype "input"))
    )
    (net (code "141") (name "unconnected-(U2-TXDEN-Pad13)") (class "Default")
      (node (ref "U2") (pin "13") (pinfunction "TXDEN_13") (pintype "input"))
    )
    (net (code "142") (name "unconnected-(U2-VCCD-Pad17)") (class "Default")
      (node (ref "U2") (pin "17") (pinfunction "VCCD_17") (pintype "output"))
    )
    (net (code "143") (name "unconnected-(U3-NC-Pad1)") (class "Default")
      (node (ref "U3") (pin "1") (pinfunction "NC_1") (pintype "bidirectional"))
    )
    (net (code "144") (name "unconnected-(U4-CSG-Pad7)") (class "Default")
      (node (ref "U4") (pin "7") (pinfunction "CSG_7") (pintype "bidirectional"))
    )
    (net (code "145") (name "unconnected-(U4-PGD-Pad3)") (class "Default")
      (node (ref "U4") (pin "3") (pinfunction "PGD_3") (pintype "bidirectional"))
    )
    (net (code "146") (name "unconnected-(U5-HOME-Pad2)") (class "Default")
      (node (ref "U5") (pin "2") (pinfunction "HOME_2") (pintype "bidirectional"))
    )
    (net (code "147") (name "unconnected-(U6-6A-Pad13)") (class "Default")
      (node (ref "U6") (pin "13") (pinfunction "6A_13") (pintype "input"))
    )
    (net (code "148") (name "unconnected-(U6-6Y-Pad12)") (class "Default")
      (node (ref "U6") (pin "12") (pinfunction "6Y_12") (pintype "output"))
    )
    (net (code "149") (name "unconnected-(U8-HOME-Pad2)") (class "Default")
      (node (ref "U8") (pin "2") (pinfunction "HOME_2") (pintype "bidirectional"))
    )
    (net (code "150") (name "unconnected-(U9-HOME-Pad2)") (class "Default")
      (node (ref "U9") (pin "2") (pinfunction "HOME_2") (pintype "bidirectional"))
    )
  )
)
